# FA_IOTv4_2_1.net
KiCad netlist of a schematic drawn in EAGLE
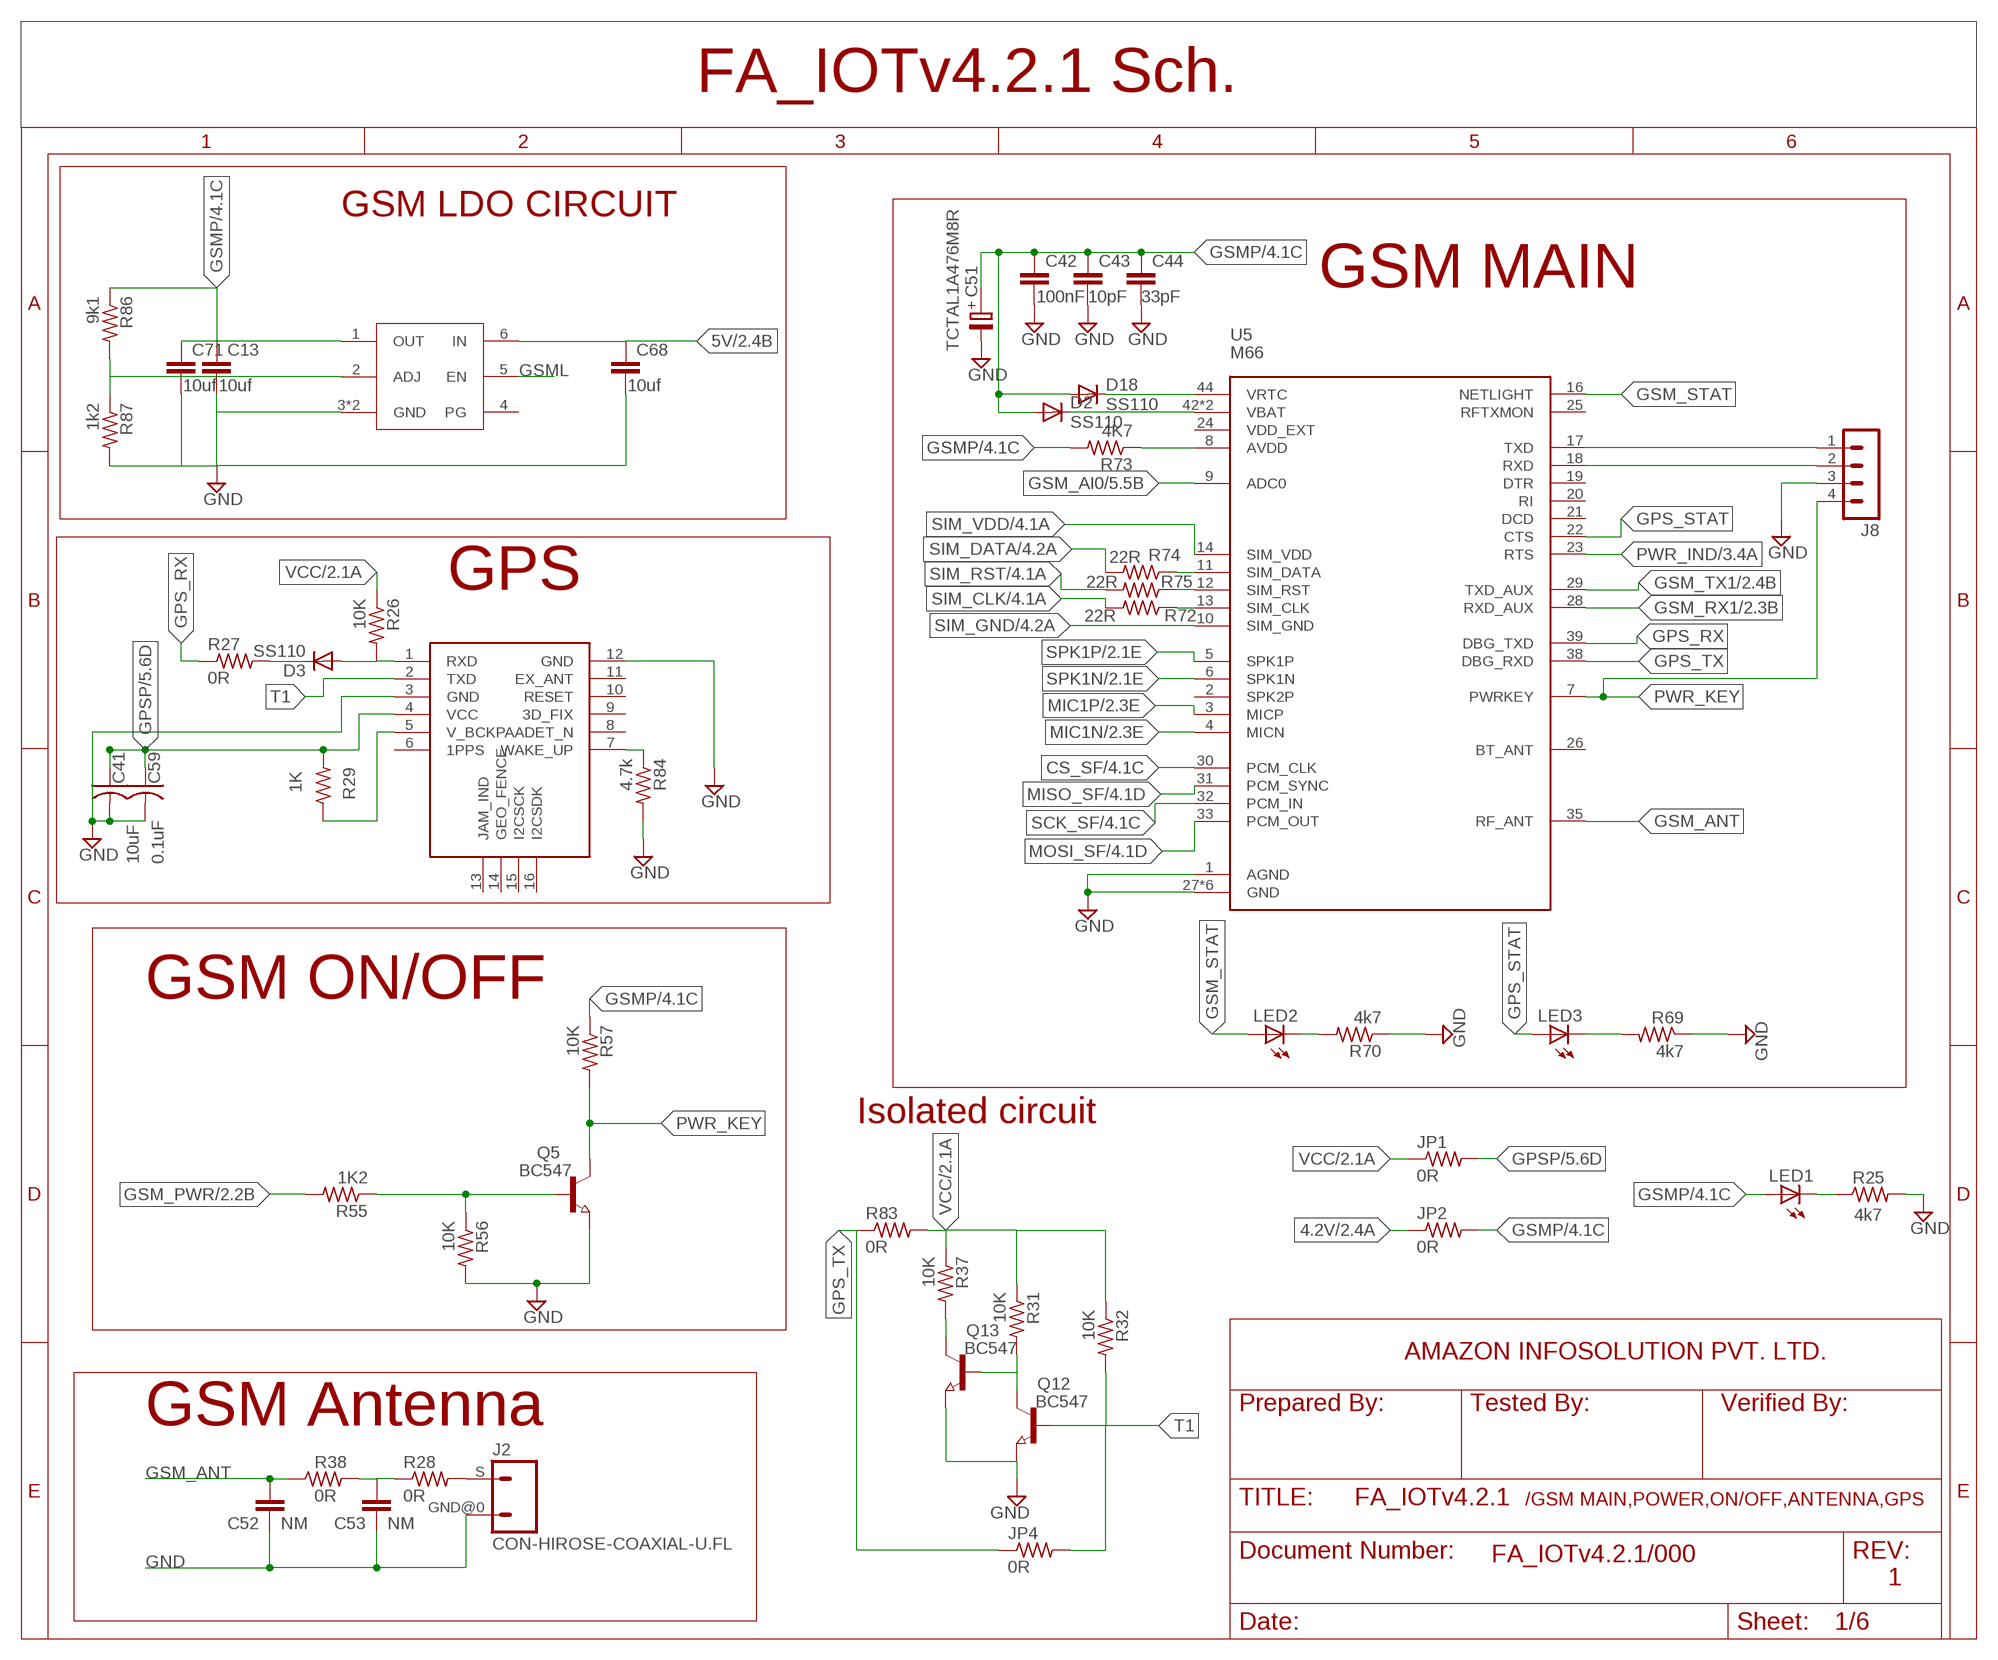
[diagram p0: schematic, sheet 1]
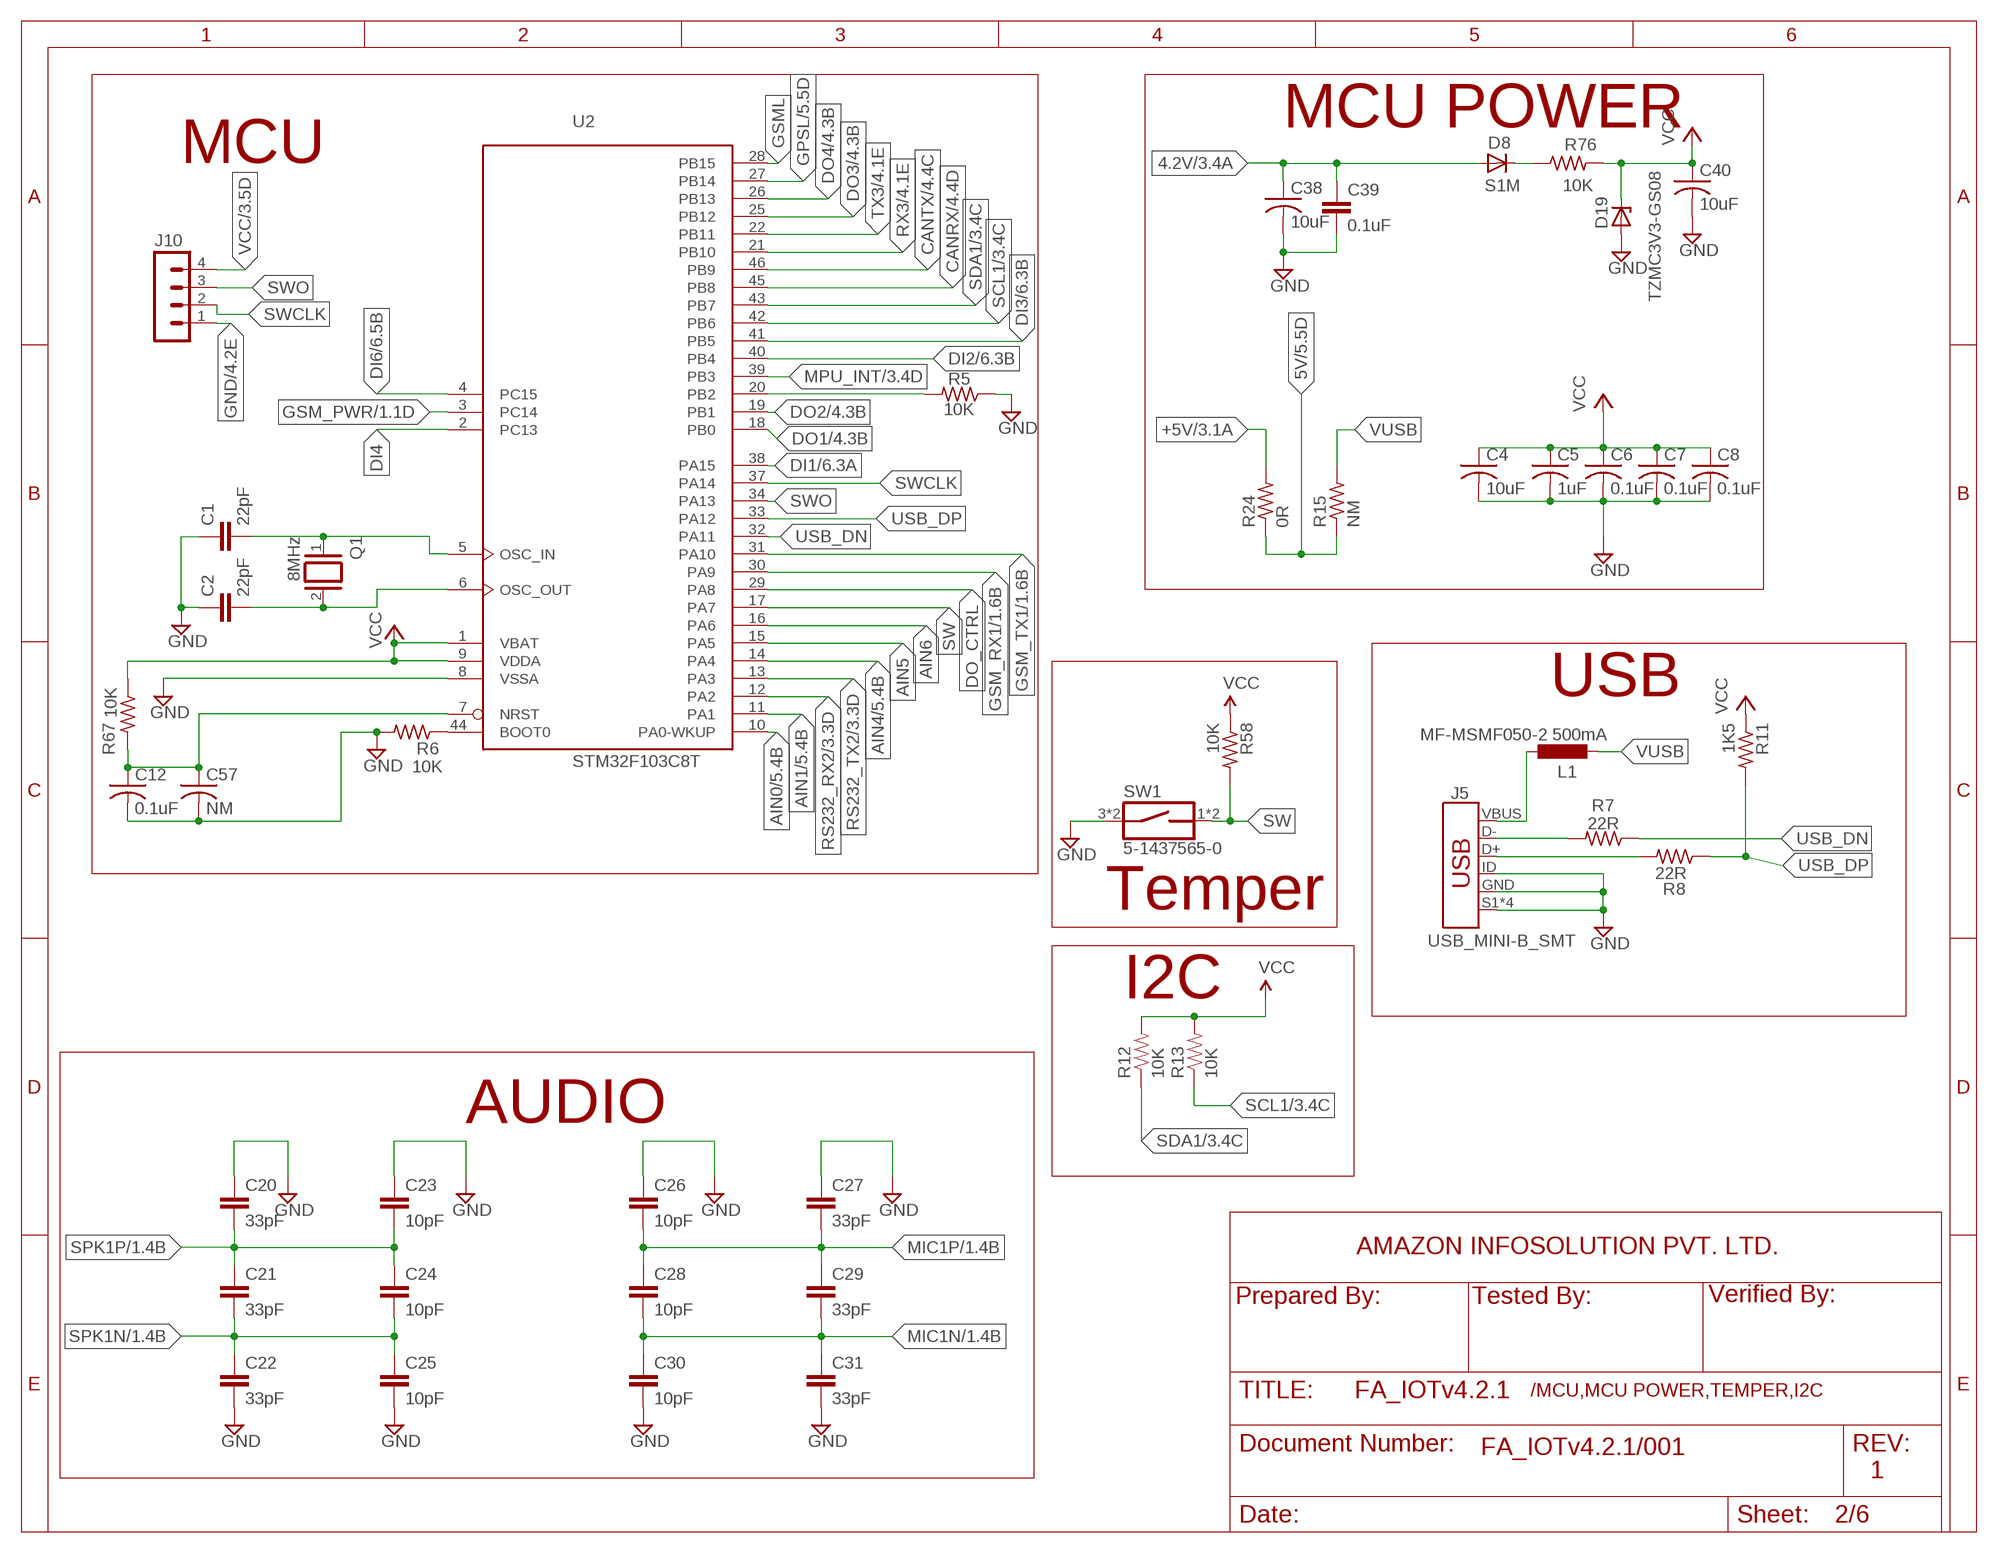
[diagram p1: schematic, sheet 2]
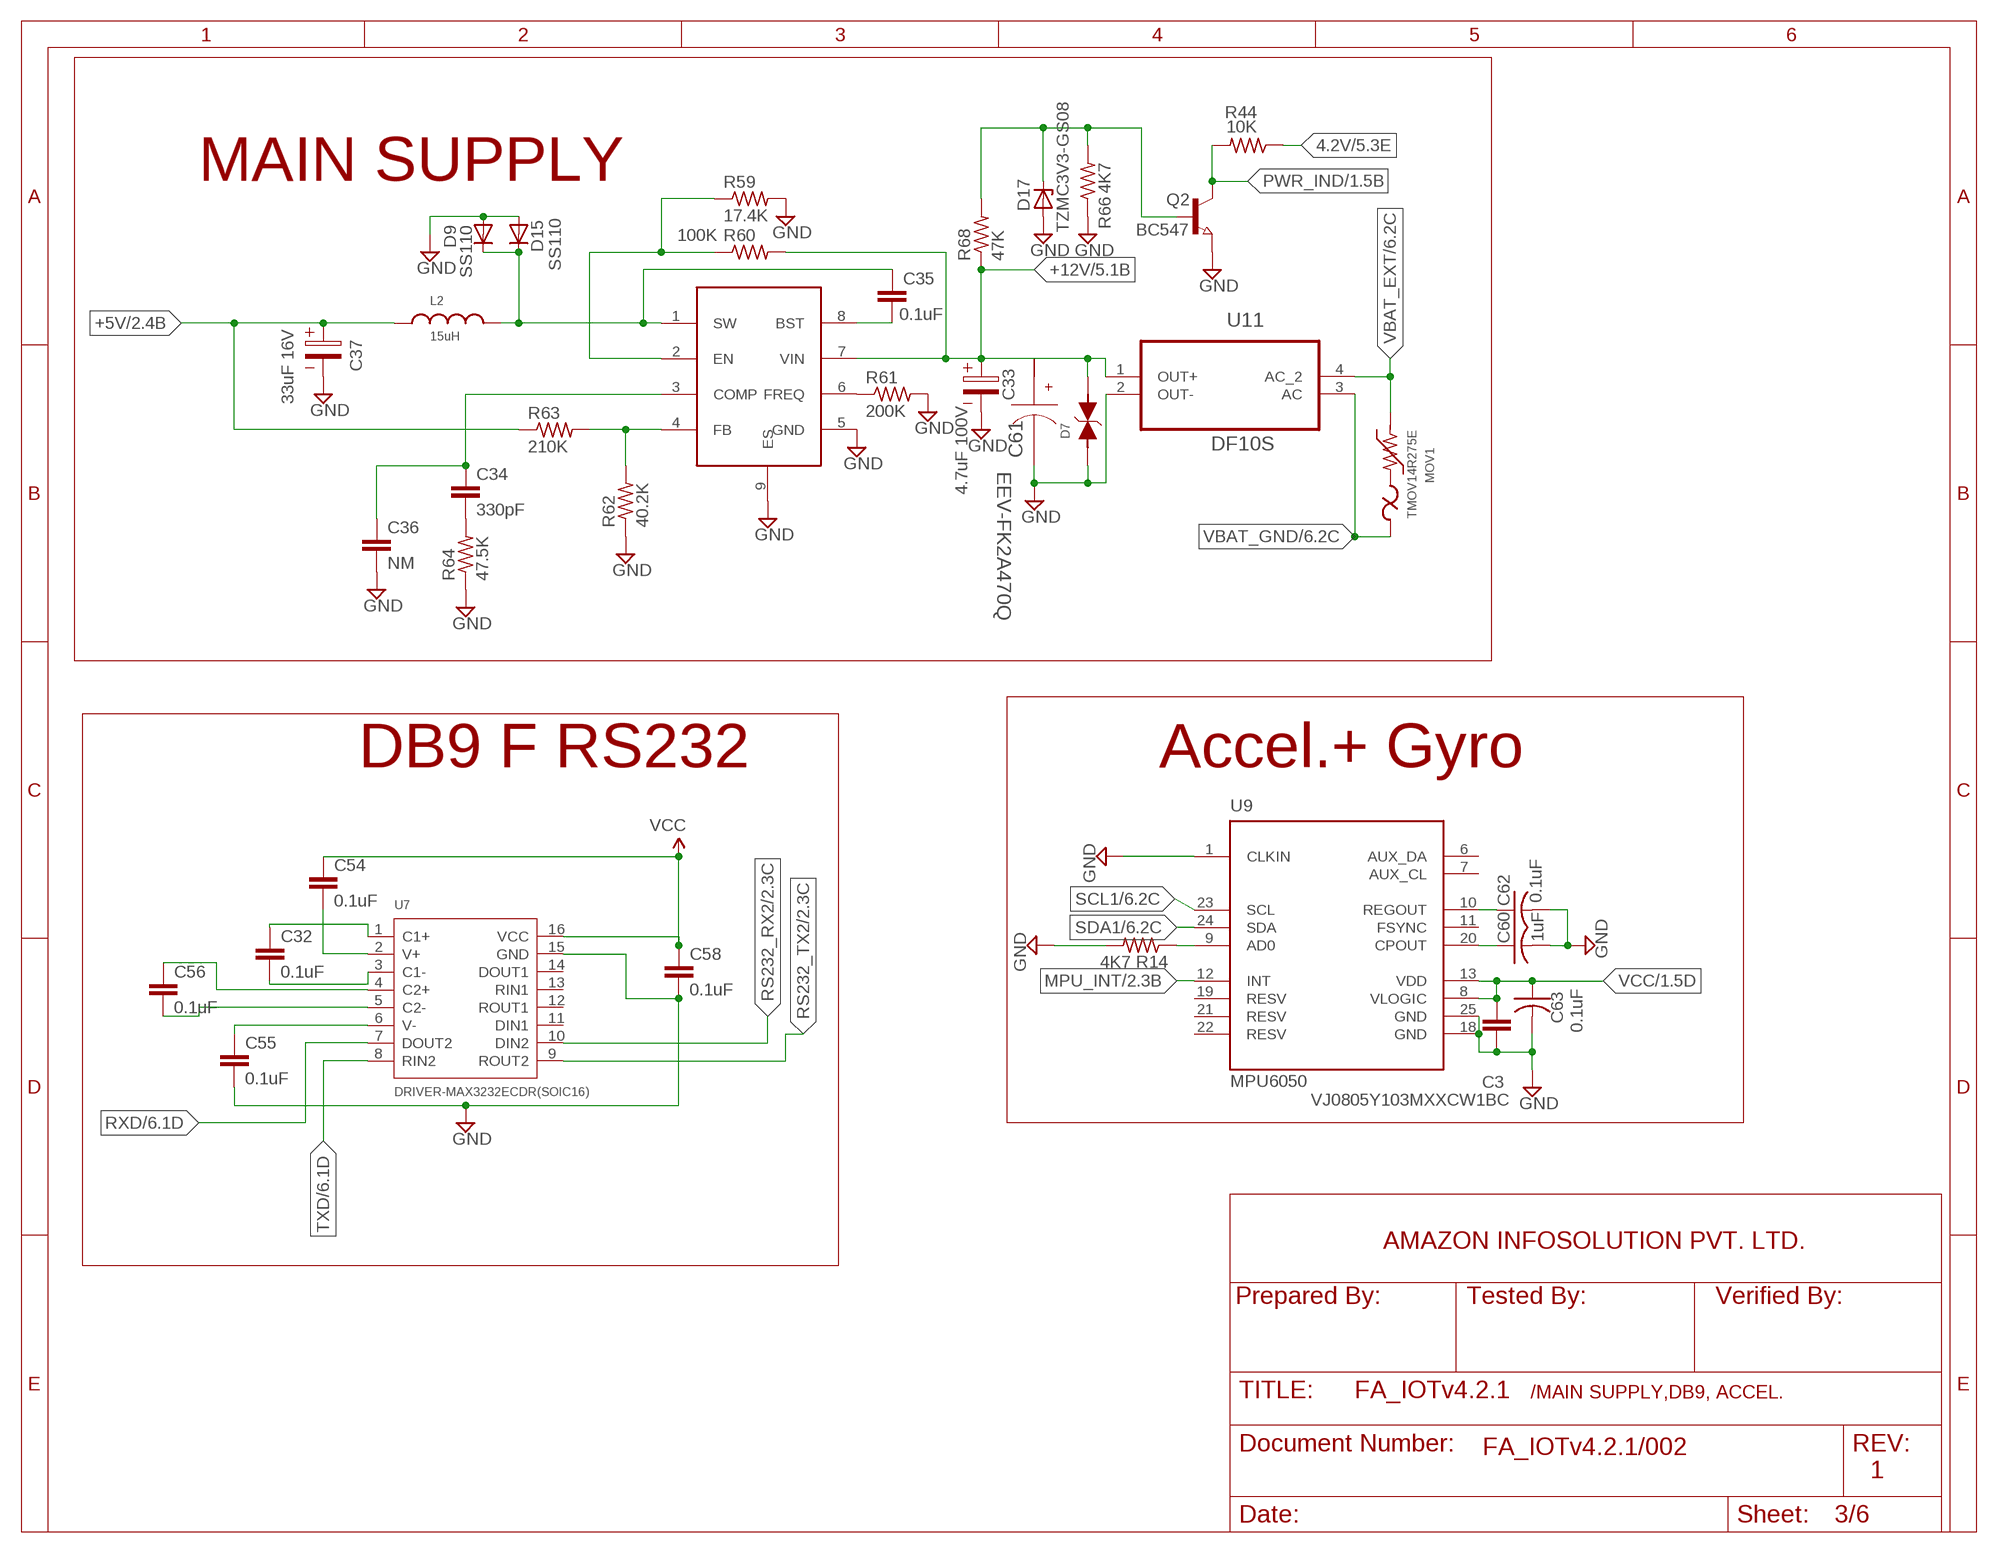
[diagram p2: schematic, sheet 3]
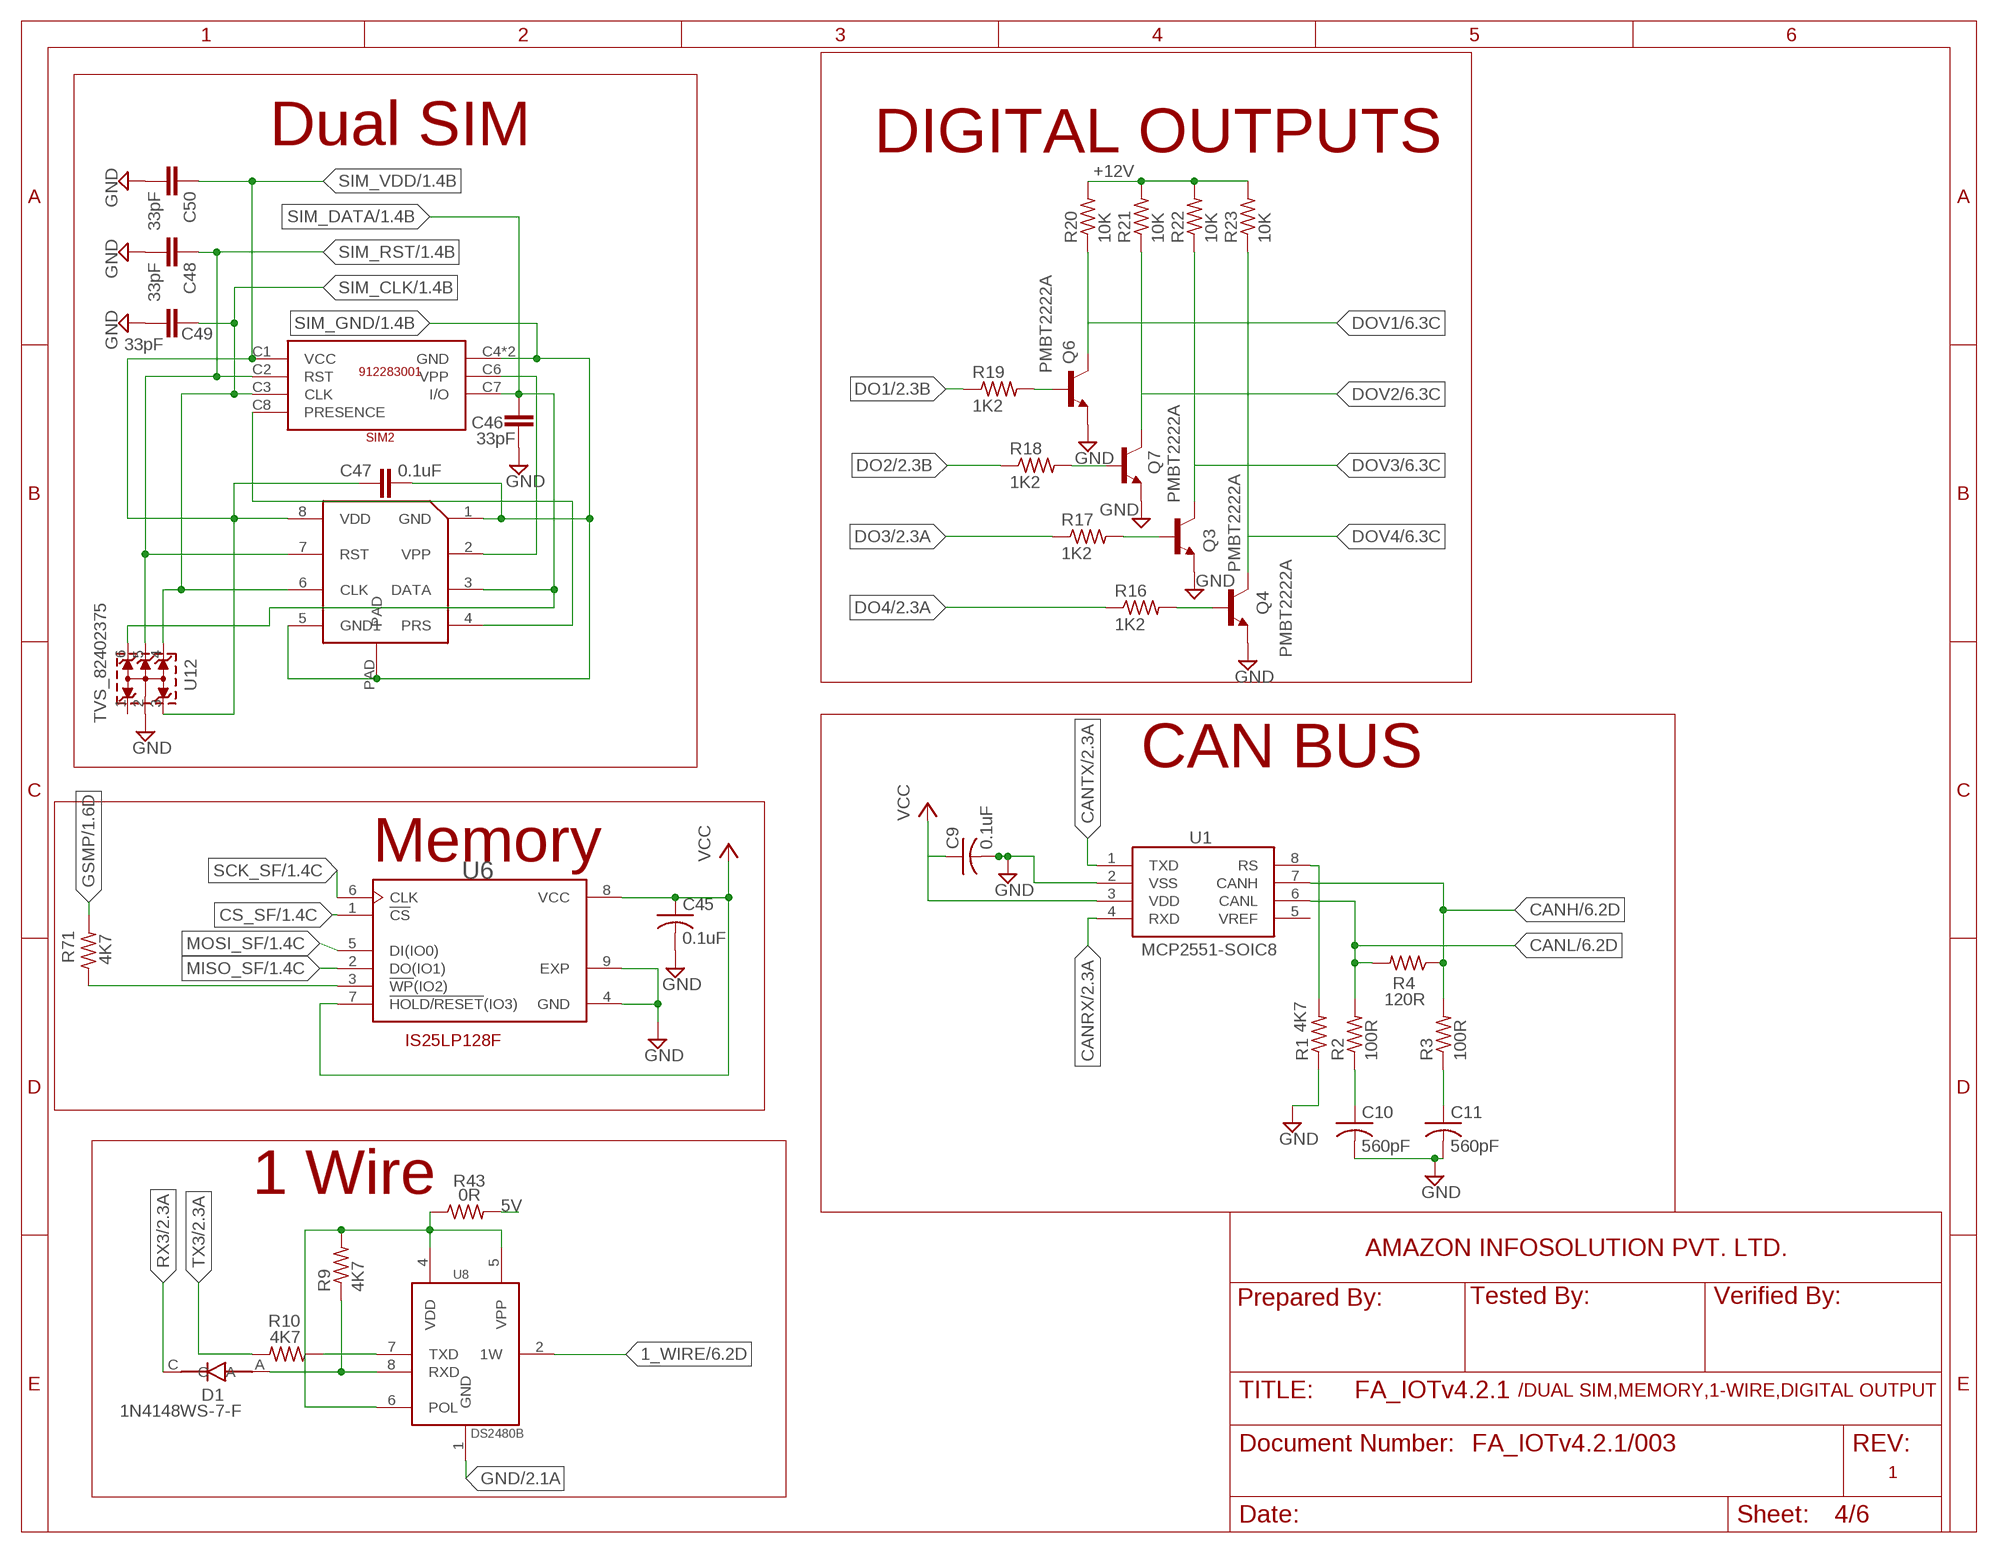
[diagram p3: schematic, sheet 4]
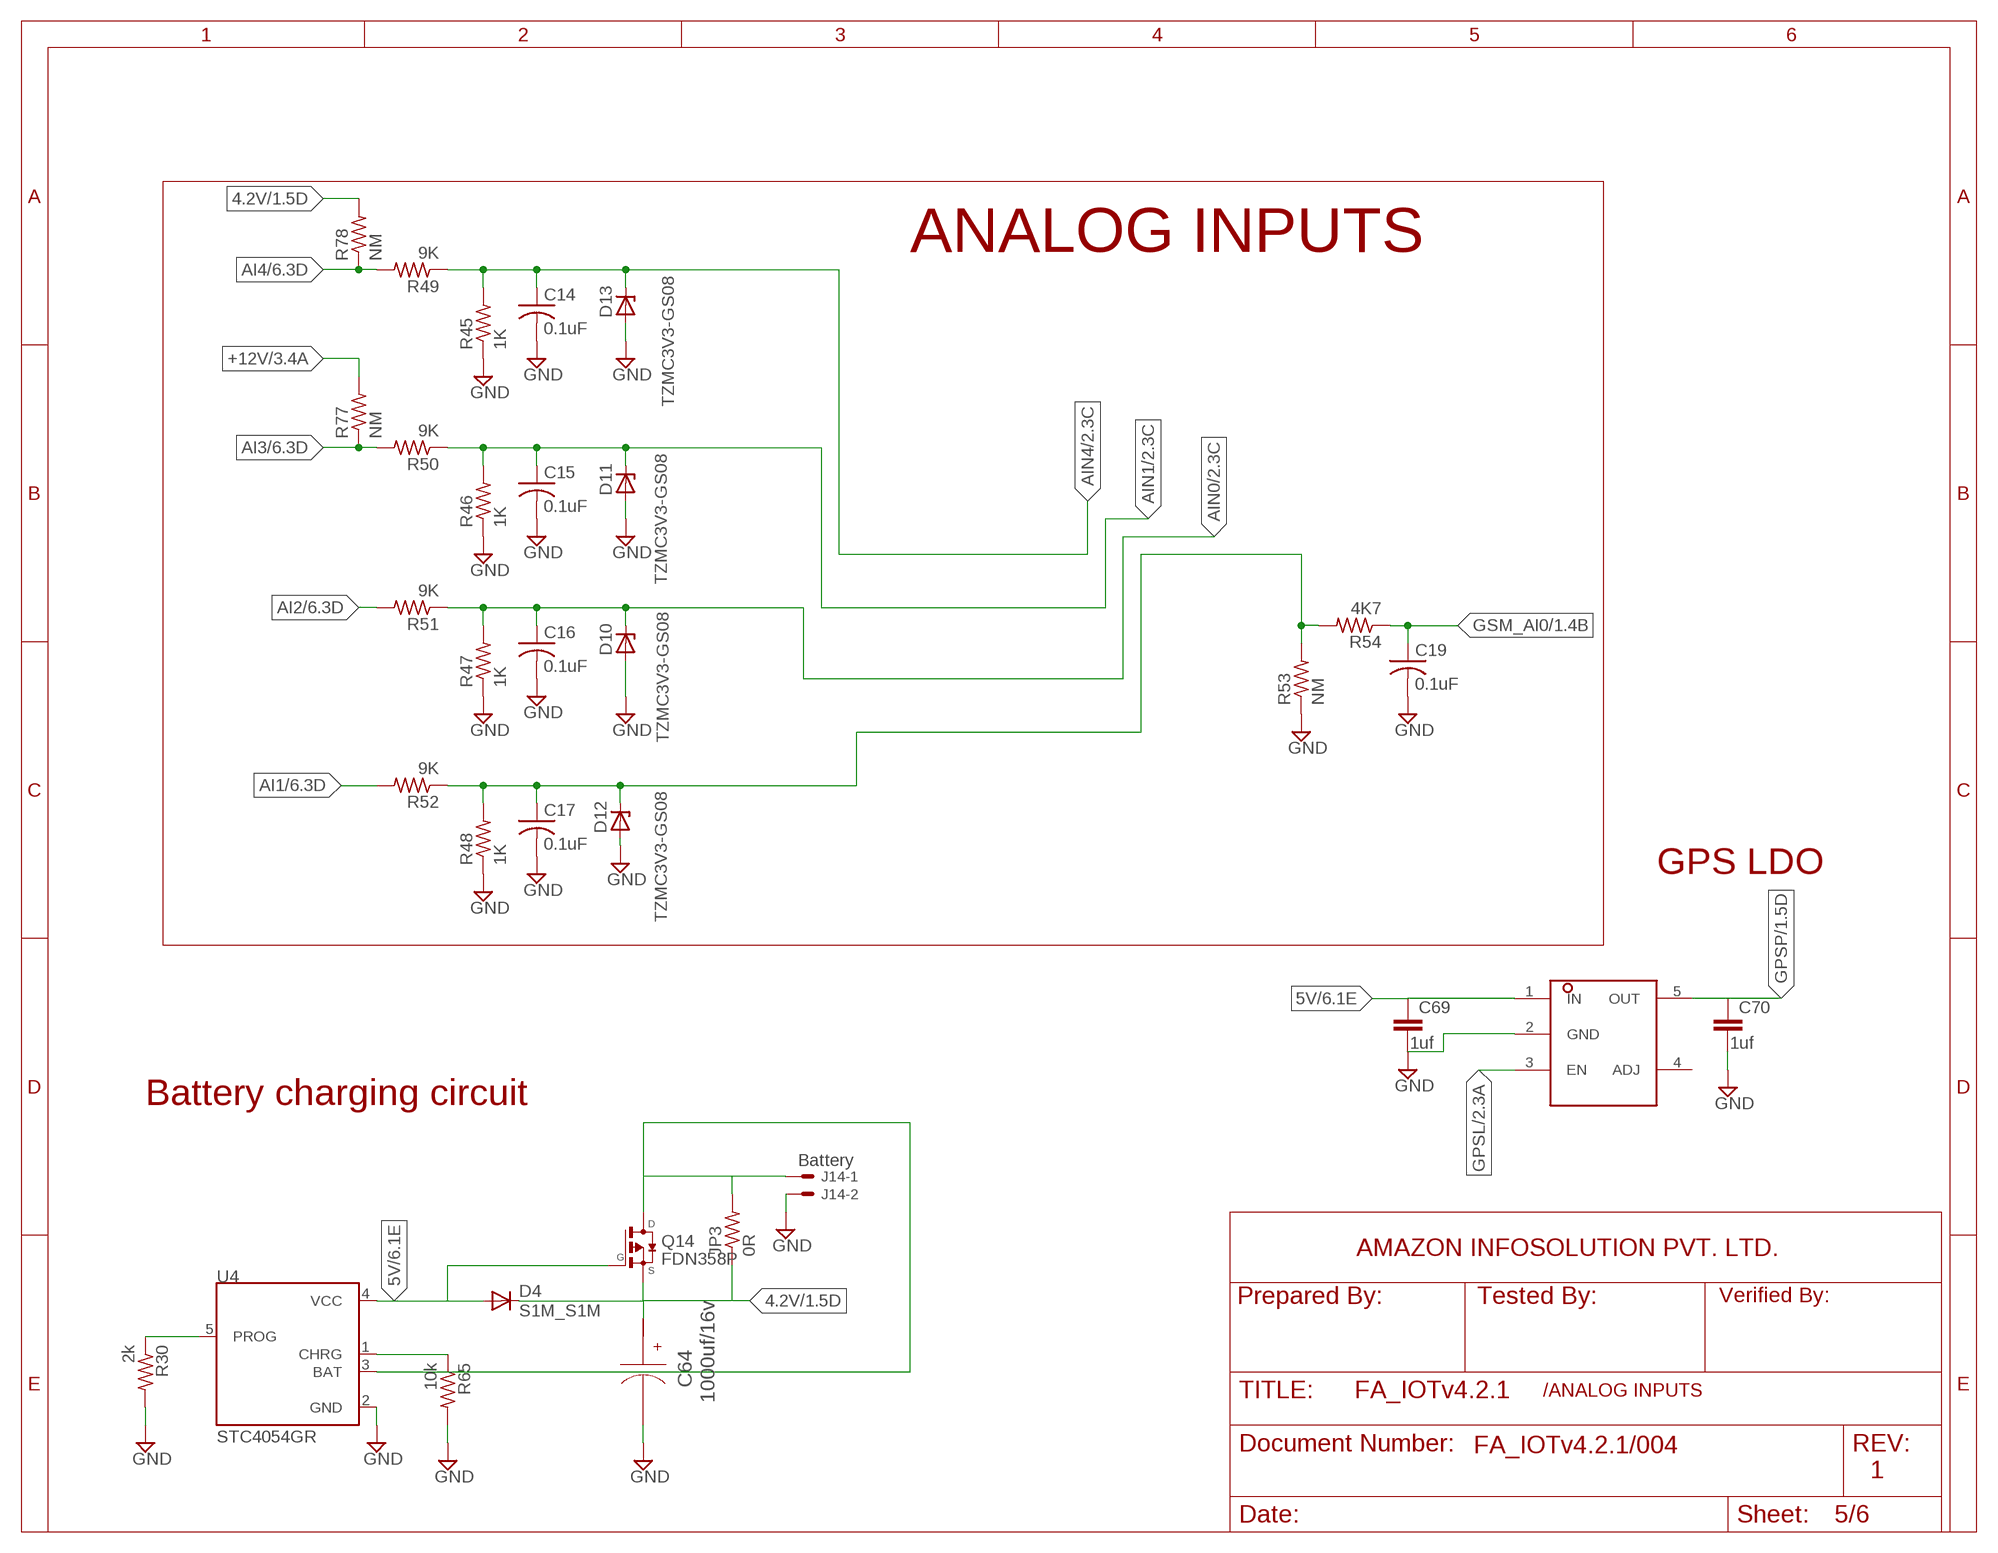
[diagram p4: schematic, sheet 5]
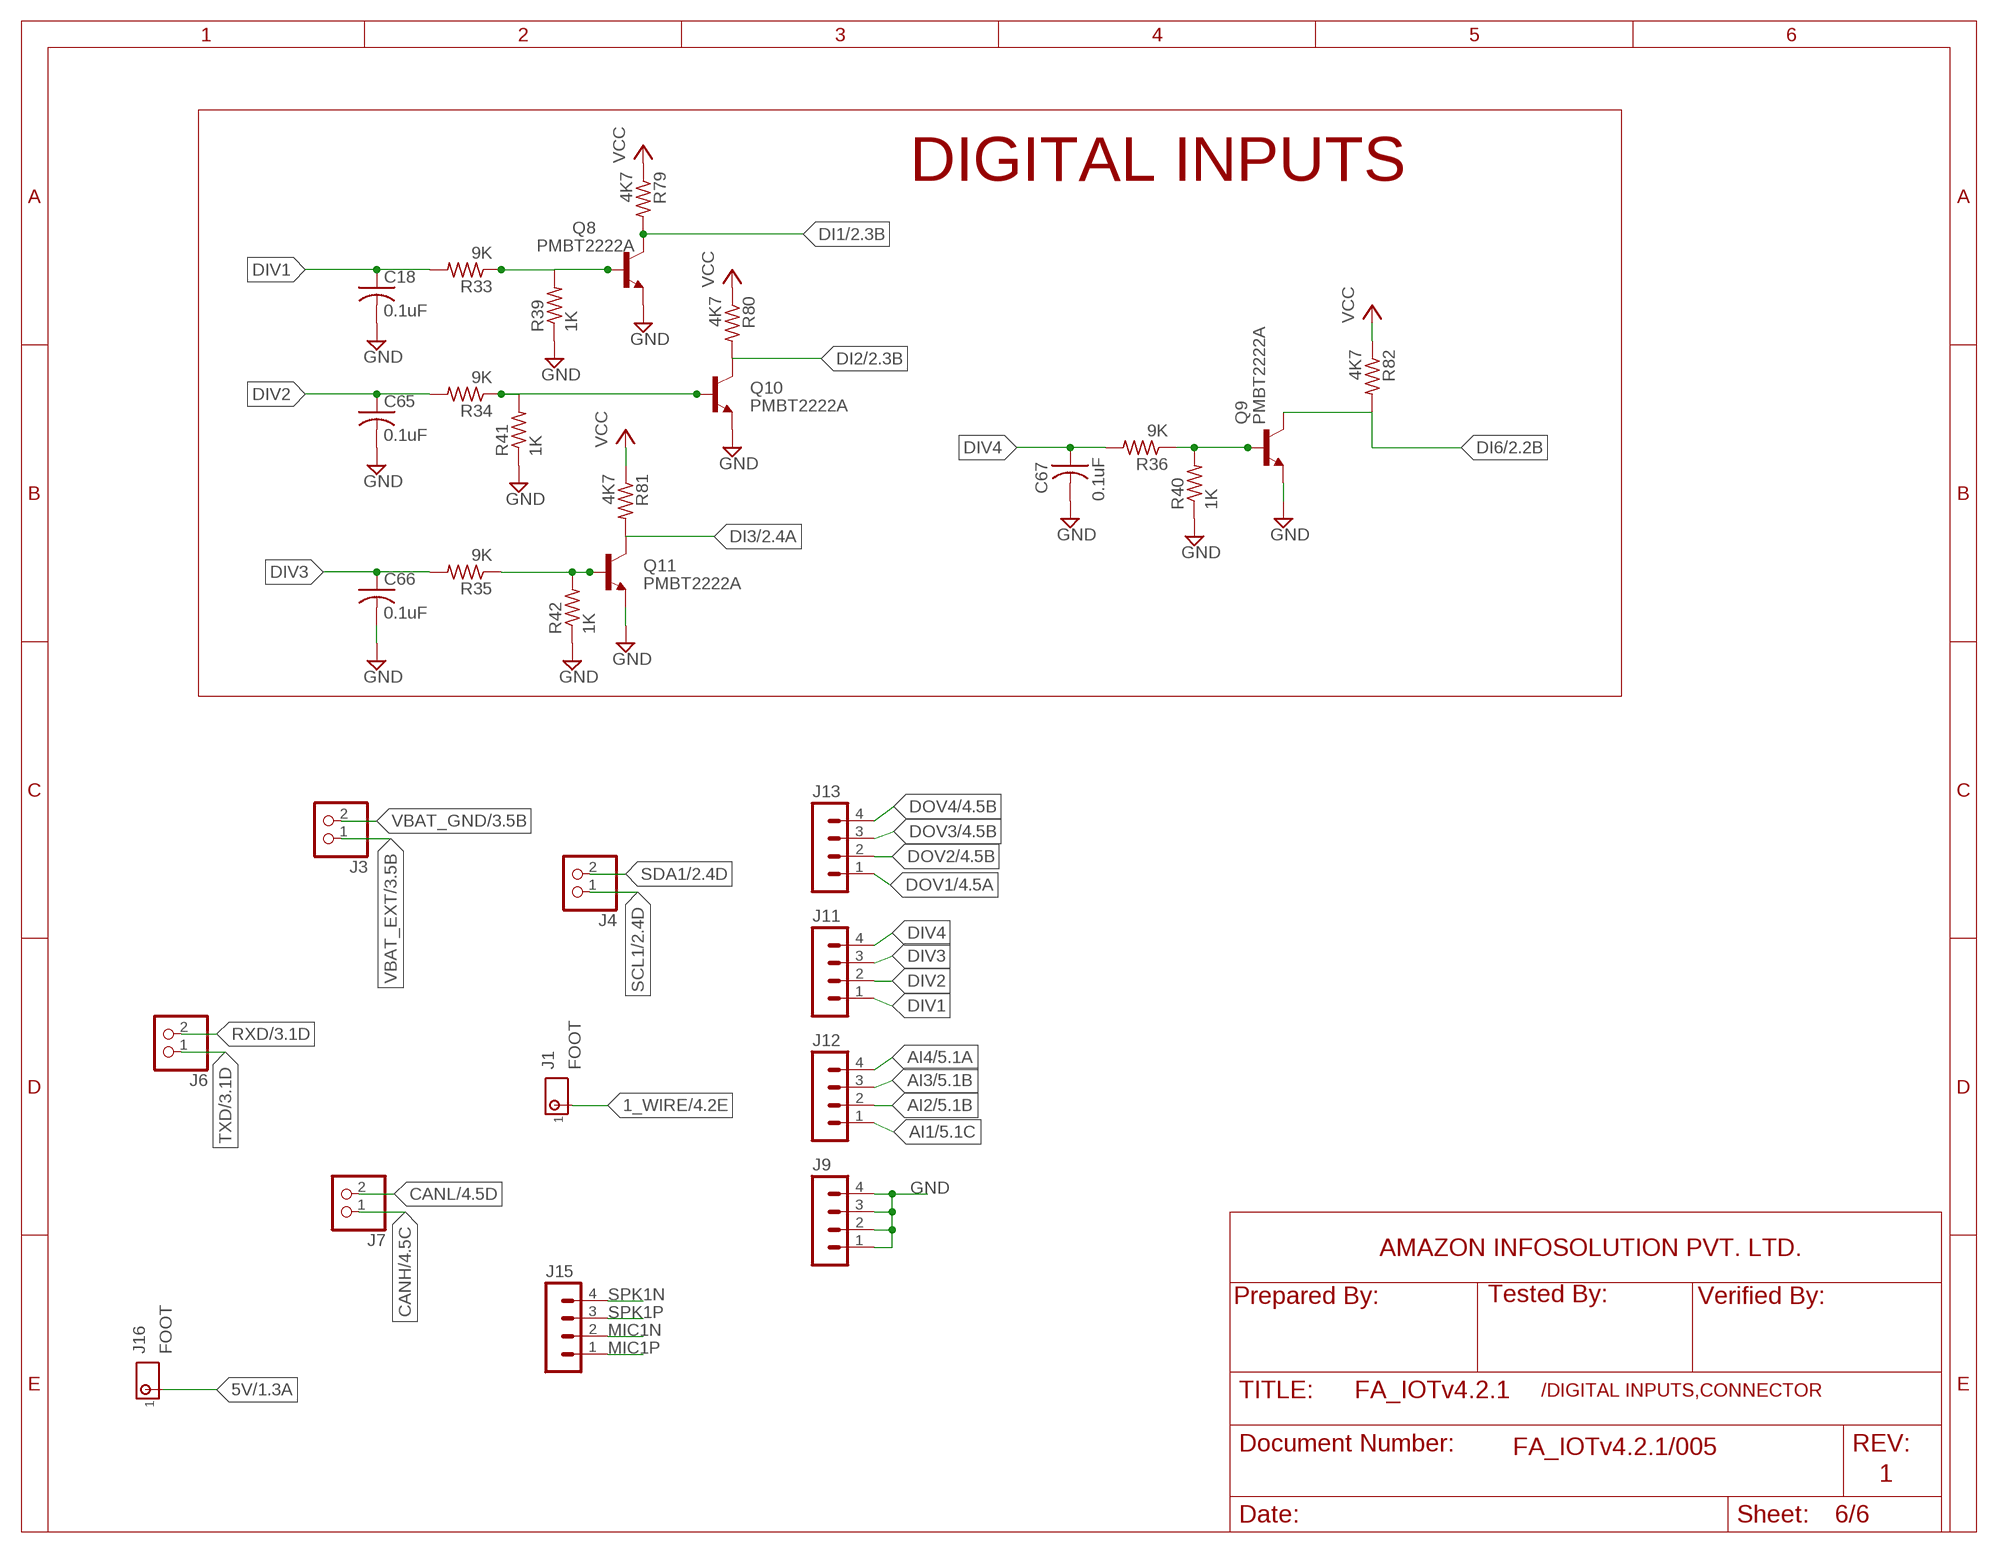
[diagram p5: schematic, sheet 6]

(export (version "E")
  (design (tool "Eeschema 10.0.6"))
  (components
    (comp (ref "C13")
      (value "10uf")
      (footprint "eagle-import:C0805")
      (libsource (lib "eagle-import") (part "resistor_C-EUC0805"))
    )
    (comp (ref "C41")
      (value "10uF")
      (footprint "eagle-import:C0805")
      (libsource (lib "eagle-import") (part "C-USC0805"))
    )
    (comp (ref "C42")
      (value "100nF")
      (footprint "eagle-import:C0805")
      (libsource (lib "eagle-import") (part "resistor_C-EUC0805"))
    )
    (comp (ref "C43")
      (value "10pF")
      (footprint "eagle-import:C0805")
      (libsource (lib "eagle-import") (part "resistor_C-EUC0805"))
    )
    (comp (ref "C44")
      (value "33pF")
      (footprint "eagle-import:C0805")
      (libsource (lib "eagle-import") (part "resistor_C-EUC0805"))
    )
    (comp (ref "C51")
      (value "TCTAL1A476M8R")
      (footprint "eagle-import:TE-A-3216")
      (libsource (lib "eagle-import") (part "C-PR-SMD-TE-A"))
    )
    (comp (ref "C52")
      (value "NM")
      (footprint "eagle-import:C0402")
      (libsource (lib "eagle-import") (part "C-EUC0402"))
    )
    (comp (ref "C53")
      (value "NM")
      (footprint "eagle-import:C0402")
      (libsource (lib "eagle-import") (part "C-EUC0402"))
    )
    (comp (ref "C59")
      (value "0.1uF")
      (footprint "eagle-import:C0402")
      (libsource (lib "eagle-import") (part "C-USC0402"))
    )
    (comp (ref "C68")
      (value "10uf")
      (footprint "eagle-import:C0805")
      (libsource (lib "eagle-import") (part "resistor_C-EUC0805"))
    )
    (comp (ref "C71")
      (value "10uf")
      (footprint "eagle-import:C0805")
      (libsource (lib "eagle-import") (part "resistor_C-EUC0805"))
    )
    (comp (ref "D2")
      (value "SS110")
      (footprint "eagle-import:DO-214AC")
      (fields (field (name "MF") "ON Semiconductor") (field (name "MP") "S1M"))
      (libsource (lib "eagle-import") (part "S1M_S1M"))
    )
    (comp (ref "D3")
      (value "SS110")
      (footprint "eagle-import:DO-214AC")
      (fields (field (name "MF") "ON Semiconductor") (field (name "MP") "S1M"))
      (libsource (lib "eagle-import") (part "S1M_S1M"))
    )
    (comp (ref "D18")
      (value "SS110")
      (footprint "eagle-import:DO-214AC")
      (fields (field (name "MF") "ON Semiconductor") (field (name "MP") "S1M"))
      (libsource (lib "eagle-import") (part "S1M_S1M"))
    )
    (comp (ref "J2")
      (value "CON-HIROSE-COAXIAL-U.FL")
      (footprint "eagle-import:CON-U.FL")
      (libsource (lib "eagle-import") (part "CON-HIROSE-COAXIAL-U.FL"))
    )
    (comp (ref "J8")
      (value "MA04-1")
      (footprint "eagle-import:MA04-1")
      (libsource (lib "eagle-import") (part "MA04-1"))
    )
    (comp (ref "JP1")
      (value "0R")
      (footprint "eagle-import:R0805")
      (libsource (lib "eagle-import") (part "resistor_R-US_R0805"))
    )
    (comp (ref "JP2")
      (value "0R")
      (footprint "eagle-import:R0805")
      (libsource (lib "eagle-import") (part "resistor_R-US_R0805"))
    )
    (comp (ref "JP4")
      (value "0R")
      (footprint "eagle-import:R0805")
      (libsource (lib "eagle-import") (part "resistor_R-US_R0805"))
    )
    (comp (ref "LED1")
      (value "LEDCHIP-LED0805")
      (footprint "eagle-import:CHIP-LED0805")
      (libsource (lib "eagle-import") (part "LEDCHIP-LED0805"))
    )
    (comp (ref "LED2")
      (value "LEDCHIP-LED0805")
      (footprint "eagle-import:CHIP-LED0805")
      (libsource (lib "eagle-import") (part "LEDCHIP-LED0805"))
    )
    (comp (ref "LED3")
      (value "LEDCHIP-LED0805")
      (footprint "eagle-import:CHIP-LED0805")
      (libsource (lib "eagle-import") (part "LEDCHIP-LED0805"))
    )
    (comp (ref "Q5")
      (value "BC547")
      (footprint "eagle-import:SOT23")
      (libsource (lib "eagle-import") (part "NPN-TRANSISTOR_SOT23"))
    )
    (comp (ref "Q12")
      (value "BC547")
      (footprint "eagle-import:SOT23")
      (libsource (lib "eagle-import") (part "NPN-TRANSISTOR_SOT23"))
    )
    (comp (ref "Q13")
      (value "BC547")
      (footprint "eagle-import:SOT23")
      (libsource (lib "eagle-import") (part "NPN-TRANSISTOR_SOT23"))
    )
    (comp (ref "R25")
      (value "4k7")
      (footprint "eagle-import:R0402")
      (libsource (lib "eagle-import") (part "R-US_R0402"))
    )
    (comp (ref "R26")
      (value "10K")
      (footprint "eagle-import:R0402")
      (libsource (lib "eagle-import") (part "resistor_R-US_R0402"))
    )
    (comp (ref "R27")
      (value "0R")
      (footprint "eagle-import:R0805")
      (libsource (lib "eagle-import") (part "resistor_R-US_R0805"))
    )
    (comp (ref "R28")
      (value "0R")
      (footprint "eagle-import:R0402")
      (libsource (lib "eagle-import") (part "resistor_R-US_R0402"))
    )
    (comp (ref "R29")
      (value "1K")
      (footprint "eagle-import:R0402")
      (libsource (lib "eagle-import") (part "resistor_R-US_R0402"))
    )
    (comp (ref "R31")
      (value "10K")
      (footprint "eagle-import:R0402")
      (libsource (lib "eagle-import") (part "resistor_R-US_R0402"))
    )
    (comp (ref "R32")
      (value "10K")
      (footprint "eagle-import:R0402")
      (libsource (lib "eagle-import") (part "resistor_R-US_R0402"))
    )
    (comp (ref "R37")
      (value "10K")
      (footprint "eagle-import:R0402")
      (libsource (lib "eagle-import") (part "resistor_R-US_R0402"))
    )
    (comp (ref "R38")
      (value "0R")
      (footprint "eagle-import:R0402")
      (libsource (lib "eagle-import") (part "resistor_R-US_R0402"))
    )
    (comp (ref "R55")
      (value "1K2")
      (footprint "eagle-import:R0402")
      (libsource (lib "eagle-import") (part "resistor_R-US_R0402"))
    )
    (comp (ref "R56")
      (value "10K")
      (footprint "eagle-import:R0402")
      (libsource (lib "eagle-import") (part "resistor_R-US_R0402"))
    )
    (comp (ref "R57")
      (value "10K")
      (footprint "eagle-import:R0402")
      (libsource (lib "eagle-import") (part "resistor_R-US_R0402"))
    )
    (comp (ref "R69")
      (value "4k7")
      (footprint "eagle-import:R0402")
      (libsource (lib "eagle-import") (part "R-US_R0402"))
    )
    (comp (ref "R70")
      (value "4k7")
      (footprint "eagle-import:R0402")
      (libsource (lib "eagle-import") (part "R-US_R0402"))
    )
    (comp (ref "R72")
      (value "22R")
      (footprint "eagle-import:R0402")
      (libsource (lib "eagle-import") (part "resistor_R-US_R0402"))
    )
    (comp (ref "R73")
      (value "4K7")
      (footprint "eagle-import:R0402")
      (libsource (lib "eagle-import") (part "resistor_R-US_R0402"))
    )
    (comp (ref "R74")
      (value "22R")
      (footprint "eagle-import:R0402")
      (libsource (lib "eagle-import") (part "resistor_R-US_R0402"))
    )
    (comp (ref "R75")
      (value "22R")
      (footprint "eagle-import:R0402")
      (libsource (lib "eagle-import") (part "resistor_R-US_R0402"))
    )
    (comp (ref "R83")
      (value "0R")
      (footprint "eagle-import:R0805")
      (libsource (lib "eagle-import") (part "resistor_R-US_R0805"))
    )
    (comp (ref "R84")
      (value "4.7k")
      (footprint "eagle-import:R0402")
      (libsource (lib "eagle-import") (part "resistor_R-US_R0402"))
    )
    (comp (ref "R86")
      (value "9k1")
      (footprint "eagle-import:R0402")
      (libsource (lib "eagle-import") (part "resistor_R-US_R0402"))
    )
    (comp (ref "R87")
      (value "1k2")
      (footprint "eagle-import:R0402")
      (libsource (lib "eagle-import") (part "resistor_R-US_R0402"))
    )
    (comp (ref "U$1")
      (value "L89")
      (footprint "eagle-import:L89")
      (libsource (lib "eagle-import") (part "L89"))
    )
    (comp (ref "U$3")
      (value "LD39200PU33R")
      (footprint "eagle-import:SON95P300X300X100-7N")
      (fields (field (name "MF") "STMicroelectronics"))
      (libsource (lib "eagle-import") (part "LD39200PU33R"))
    )
    (comp (ref "U5")
      (value "M66")
      (footprint "eagle-import:M66")
      (libsource (lib "eagle-import") (part "M66"))
    )
    (comp (ref "C9")
      (value "0.1uF")
      (footprint "eagle-import:C0805")
      (libsource (lib "eagle-import") (part "C-USC0805"))
    )
    (comp (ref "C10")
      (value "560pF")
      (footprint "eagle-import:C0402")
      (libsource (lib "eagle-import") (part "C-USC0402"))
    )
    (comp (ref "C11")
      (value "560pF")
      (footprint "eagle-import:C0402")
      (libsource (lib "eagle-import") (part "C-USC0402"))
    )
    (comp (ref "C45")
      (value "0.1uF")
      (footprint "eagle-import:C0402")
      (libsource (lib "eagle-import") (part "C-USC0402"))
    )
    (comp (ref "C46")
      (value "33pF")
      (footprint "eagle-import:C0805")
      (libsource (lib "eagle-import") (part "resistor_C-EUC0805"))
    )
    (comp (ref "C47")
      (value "0.1uF")
      (footprint "eagle-import:C0805")
      (libsource (lib "eagle-import") (part "resistor_C-EUC0805"))
    )
    (comp (ref "C48")
      (value "33pF")
      (footprint "eagle-import:C0805")
      (libsource (lib "eagle-import") (part "resistor_C-EUC0805"))
    )
    (comp (ref "C49")
      (value "33pF")
      (footprint "eagle-import:C0805")
      (libsource (lib "eagle-import") (part "resistor_C-EUC0805"))
    )
    (comp (ref "C50")
      (value "33pF")
      (footprint "eagle-import:C0805")
      (libsource (lib "eagle-import") (part "resistor_C-EUC0805"))
    )
    (comp (ref "D1")
      (value "1N4148WS-7-F")
      (footprint "eagle-import:SOD2513X120N")
      (fields (field (name "MF") "Diodes Inc."))
      (libsource (lib "eagle-import") (part "1N4148WS-7-F"))
    )
    (comp (ref "Q3")
      (value "PMBT2222A")
      (footprint "eagle-import:SOT23-BEC")
      (fields (field (name "MF") "NXP Semiconductors"))
      (libsource (lib "eagle-import") (part "PMBT2222A"))
    )
    (comp (ref "Q4")
      (value "PMBT2222A")
      (footprint "eagle-import:SOT23-BEC")
      (fields (field (name "MF") "NXP Semiconductors"))
      (libsource (lib "eagle-import") (part "PMBT2222A"))
    )
    (comp (ref "Q6")
      (value "PMBT2222A")
      (footprint "eagle-import:SOT23-BEC")
      (fields (field (name "MF") "NXP Semiconductors"))
      (libsource (lib "eagle-import") (part "PMBT2222A"))
    )
    (comp (ref "Q7")
      (value "PMBT2222A")
      (footprint "eagle-import:SOT23-BEC")
      (fields (field (name "MF") "NXP Semiconductors"))
      (libsource (lib "eagle-import") (part "PMBT2222A"))
    )
    (comp (ref "R1")
      (value "4K7")
      (footprint "eagle-import:R0402")
      (libsource (lib "eagle-import") (part "resistor_R-US_R0402"))
    )
    (comp (ref "R2")
      (value "100R")
      (footprint "eagle-import:R0402")
      (libsource (lib "eagle-import") (part "resistor_R-US_R0402"))
    )
    (comp (ref "R3")
      (value "100R")
      (footprint "eagle-import:R0402")
      (libsource (lib "eagle-import") (part "resistor_R-US_R0402"))
    )
    (comp (ref "R4")
      (value "120R")
      (footprint "eagle-import:R0402")
      (libsource (lib "eagle-import") (part "resistor_R-US_R0402"))
    )
    (comp (ref "R9")
      (value "4K7")
      (footprint "eagle-import:R0402")
      (libsource (lib "eagle-import") (part "resistor_R-US_R0402"))
    )
    (comp (ref "R10")
      (value "4K7")
      (footprint "eagle-import:R0402")
      (libsource (lib "eagle-import") (part "resistor_R-US_R0402"))
    )
    (comp (ref "R16")
      (value "1K2")
      (footprint "eagle-import:R0402")
      (libsource (lib "eagle-import") (part "resistor_R-US_R0402"))
    )
    (comp (ref "R17")
      (value "1K2")
      (footprint "eagle-import:R0402")
      (libsource (lib "eagle-import") (part "resistor_R-US_R0402"))
    )
    (comp (ref "R18")
      (value "1K2")
      (footprint "eagle-import:R0402")
      (libsource (lib "eagle-import") (part "resistor_R-US_R0402"))
    )
    (comp (ref "R19")
      (value "1K2")
      (footprint "eagle-import:R0402")
      (libsource (lib "eagle-import") (part "resistor_R-US_R0402"))
    )
    (comp (ref "R20")
      (value "10K")
      (footprint "eagle-import:R0805")
      (libsource (lib "eagle-import") (part "resistor_R-US_R0805"))
    )
    (comp (ref "R21")
      (value "10K")
      (footprint "eagle-import:R0805")
      (libsource (lib "eagle-import") (part "resistor_R-US_R0805"))
    )
    (comp (ref "R22")
      (value "10K")
      (footprint "eagle-import:R0805")
      (libsource (lib "eagle-import") (part "resistor_R-US_R0805"))
    )
    (comp (ref "R23")
      (value "10K")
      (footprint "eagle-import:R0805")
      (libsource (lib "eagle-import") (part "resistor_R-US_R0805"))
    )
    (comp (ref "R43")
      (value "0R")
      (footprint "eagle-import:R0805")
      (libsource (lib "eagle-import") (part "resistor_R-US_R0805"))
    )
    (comp (ref "R71")
      (value "4K7")
      (footprint "eagle-import:R0402")
      (libsource (lib "eagle-import") (part "R-US_R0402"))
    )
    (comp (ref "SIM1")
      (value "MFF2_SIM")
      (footprint "eagle-import:MFF2DFN8")
      (libsource (lib "eagle-import") (part "MFF2_SIM"))
    )
    (comp (ref "SIM2")
      (value "912283001")
      (footprint "eagle-import:91228-3001")
      (fields (field (name "MF") "Molex") (field (name "MP") "91228-3001"))
      (libsource (lib "eagle-import") (part "912283001"))
    )
    (comp (ref "U1")
      (value "MCP2551-SOIC8")
      (footprint "eagle-import:SOIC8-6.0")
      (libsource (lib "eagle-import") (part "MCP2551-SOIC8"))
    )
    (comp (ref "U6")
      (value "W25Q32FVZPIG_TR")
      (footprint "eagle-import:SON127P600X500X80-9N")
      (fields (field (name "MF") "Winbond") (field (name "MP") "W25Q32FVZPIG TR"))
      (libsource (lib "eagle-import") (part "W25Q32FVZPIG_TR"))
    )
    (comp (ref "U8")
      (value "DS2480B")
      (footprint "eagle-import:SO08")
      (fields (field (name "MF") "Maxim Integrated"))
      (libsource (lib "eagle-import") (part "DS2480B"))
    )
    (comp (ref "U12")
      (value "TVS_82402375")
      (footprint "eagle-import:WE-TVS_SC70-6L")
      (fields (field (name "MF") "Wurth Electronics") (field (name "MP") "82402375"))
      (libsource (lib "eagle-import") (part "WE-TVS_82402375"))
    )
    (comp (ref "C14")
      (value "0.1uF")
      (footprint "eagle-import:C0402")
      (libsource (lib "eagle-import") (part "C-USC0402"))
    )
    (comp (ref "C15")
      (value "0.1uF")
      (footprint "eagle-import:C0402")
      (libsource (lib "eagle-import") (part "C-USC0402"))
    )
    (comp (ref "C16")
      (value "0.1uF")
      (footprint "eagle-import:C0402")
      (libsource (lib "eagle-import") (part "C-USC0402"))
    )
    (comp (ref "C17")
      (value "0.1uF")
      (footprint "eagle-import:C0402")
      (libsource (lib "eagle-import") (part "C-USC0402"))
    )
    (comp (ref "C19")
      (value "0.1uF")
      (footprint "eagle-import:C0402")
      (libsource (lib "eagle-import") (part "C-USC0402"))
    )
    (comp (ref "C64")
      (value "1000uf/16v")
      (footprint "eagle-import:SM_RADIAL_H13")
      (fields (field (name "MF") "Panasonic") (field (name "MP") "EEV-FK2A470Q"))
      (libsource (lib "eagle-import") (part "EEV-FK2A470Q"))
    )
    (comp (ref "C69")
      (value "1uf")
      (footprint "eagle-import:C0603")
      (libsource (lib "eagle-import") (part "resistor_C-EUC0603"))
    )
    (comp (ref "C70")
      (value "1uf")
      (footprint "eagle-import:C0603")
      (libsource (lib "eagle-import") (part "resistor_C-EUC0603"))
    )
    (comp (ref "D4")
      (value "S1M_S1M")
      (footprint "eagle-import:S1M_DO-214AC")
      (fields (field (name "MF") "ON Semiconductor") (field (name "MP") "S1M"))
      (libsource (lib "eagle-import") (part "S1M_S1M"))
    )
    (comp (ref "D10")
      (value "TZMC3V3-GS08")
      (footprint "eagle-import:SOD80C")
      (libsource (lib "eagle-import") (part "ZENER-DIODESOD80C"))
    )
    (comp (ref "D11")
      (value "TZMC3V3-GS08")
      (footprint "eagle-import:SOD80C")
      (libsource (lib "eagle-import") (part "ZENER-DIODESOD80C"))
    )
    (comp (ref "D12")
      (value "TZMC3V3-GS08")
      (footprint "eagle-import:SOD80C")
      (libsource (lib "eagle-import") (part "ZENER-DIODESOD80C"))
    )
    (comp (ref "D13")
      (value "TZMC3V3-GS08")
      (footprint "eagle-import:SOD80C")
      (libsource (lib "eagle-import") (part "ZENER-DIODESOD80C"))
    )
    (comp (ref "J14")
      (value "Battery")
      (footprint "eagle-import:6410-02")
      (libsource (lib "eagle-import") (part "22-?-0227-2021"))
    )
    (comp (ref "JP3")
      (value "0R")
      (footprint "eagle-import:R0805")
      (libsource (lib "eagle-import") (part "resistor_R-US_R0805"))
    )
    (comp (ref "Q14")
      (value "FDN358P")
      (footprint "eagle-import:SSOT-3")
      (fields (field (name "MF") "ON Semiconductor"))
      (libsource (lib "eagle-import") (part "FDN358P"))
    )
    (comp (ref "R30")
      (value "2k")
      (footprint "eagle-import:R0402")
      (libsource (lib "eagle-import") (part "resistor_R-US_R0402"))
    )
    (comp (ref "R45")
      (value "1K")
      (footprint "eagle-import:R0402")
      (libsource (lib "eagle-import") (part "resistor_R-US_R0402"))
    )
    (comp (ref "R46")
      (value "1K")
      (footprint "eagle-import:R0402")
      (libsource (lib "eagle-import") (part "resistor_R-US_R0402"))
    )
    (comp (ref "R47")
      (value "1K")
      (footprint "eagle-import:R0402")
      (libsource (lib "eagle-import") (part "resistor_R-US_R0402"))
    )
    (comp (ref "R48")
      (value "1K")
      (footprint "eagle-import:R0402")
      (libsource (lib "eagle-import") (part "resistor_R-US_R0402"))
    )
    (comp (ref "R49")
      (value "9K")
      (footprint "eagle-import:R0402")
      (libsource (lib "eagle-import") (part "resistor_R-US_R0402"))
    )
    (comp (ref "R50")
      (value "9K")
      (footprint "eagle-import:R0402")
      (libsource (lib "eagle-import") (part "resistor_R-US_R0402"))
    )
    (comp (ref "R51")
      (value "9K")
      (footprint "eagle-import:R0402")
      (libsource (lib "eagle-import") (part "resistor_R-US_R0402"))
    )
    (comp (ref "R52")
      (value "9K")
      (footprint "eagle-import:R0402")
      (libsource (lib "eagle-import") (part "resistor_R-US_R0402"))
    )
    (comp (ref "R53")
      (value "NM")
      (footprint "eagle-import:R0402")
      (libsource (lib "eagle-import") (part "resistor_R-US_R0402"))
    )
    (comp (ref "R54")
      (value "4K7")
      (footprint "eagle-import:R0402")
      (libsource (lib "eagle-import") (part "resistor_R-US_R0402"))
    )
    (comp (ref "R65")
      (value "10k")
      (footprint "eagle-import:R0402")
      (libsource (lib "eagle-import") (part "resistor_R-US_R0402"))
    )
    (comp (ref "R77")
      (value "NM")
      (footprint "eagle-import:R0805")
      (libsource (lib "eagle-import") (part "resistor_R-US_R0805"))
    )
    (comp (ref "R78")
      (value "NM")
      (footprint "eagle-import:R0805")
      (libsource (lib "eagle-import") (part "resistor_R-US_R0805"))
    )
    (comp (ref "U$4")
      (value "LDK220M33R")
      (footprint "eagle-import:SOT95P280X145-5N")
      (libsource (lib "eagle-import") (part "LDK220M33R"))
    )
    (comp (ref "U4")
      (value "STC4054GR")
      (footprint "eagle-import:SOT95P280X110-5N")
      (fields (field (name "MF") "STMicroelectronics"))
      (libsource (lib "eagle-import") (part "STC4054GR"))
    )
    (comp (ref "C18")
      (value "0.1uF")
      (footprint "eagle-import:C0402")
      (libsource (lib "eagle-import") (part "C-USC0402"))
    )
    (comp (ref "C65")
      (value "0.1uF")
      (footprint "eagle-import:C0402")
      (libsource (lib "eagle-import") (part "C-USC0402"))
    )
    (comp (ref "C66")
      (value "0.1uF")
      (footprint "eagle-import:C0402")
      (libsource (lib "eagle-import") (part "C-USC0402"))
    )
    (comp (ref "C67")
      (value "0.1uF")
      (footprint "eagle-import:C0402")
      (libsource (lib "eagle-import") (part "C-USC0402"))
    )
    (comp (ref "J1")
      (value "FOOT")
      (footprint "eagle-import:FOOT")
      (libsource (lib "eagle-import") (part "FOOT"))
    )
    (comp (ref "J3")
      (value "PINHD-1X2")
      (footprint "eagle-import:1X02")
      (libsource (lib "eagle-import") (part "PINHD-1X2"))
    )
    (comp (ref "J4")
      (value "PINHD-1X2")
      (footprint "eagle-import:1X02")
      (libsource (lib "eagle-import") (part "PINHD-1X2"))
    )
    (comp (ref "J6")
      (value "PINHD-1X2")
      (footprint "eagle-import:1X02")
      (libsource (lib "eagle-import") (part "PINHD-1X2"))
    )
    (comp (ref "J7")
      (value "PINHD-1X2")
      (footprint "eagle-import:1X02")
      (libsource (lib "eagle-import") (part "PINHD-1X2"))
    )
    (comp (ref "J9")
      (value "MA04-1")
      (footprint "eagle-import:MA04-1")
      (libsource (lib "eagle-import") (part "MA04-1"))
    )
    (comp (ref "J11")
      (value "MA04-1")
      (footprint "eagle-import:MA04-1")
      (libsource (lib "eagle-import") (part "MA04-1"))
    )
    (comp (ref "J12")
      (value "MA04-1")
      (footprint "eagle-import:MA04-1")
      (libsource (lib "eagle-import") (part "MA04-1"))
    )
    (comp (ref "J13")
      (value "MA04-1")
      (footprint "eagle-import:MA04-1")
      (libsource (lib "eagle-import") (part "MA04-1"))
    )
    (comp (ref "J15")
      (value "MA04-1")
      (footprint "eagle-import:MA04-1")
      (libsource (lib "eagle-import") (part "MA04-1"))
    )
    (comp (ref "J16")
      (value "FOOT")
      (footprint "eagle-import:FOOT")
      (libsource (lib "eagle-import") (part "FOOT"))
    )
    (comp (ref "Q8")
      (value "PMBT2222A")
      (footprint "eagle-import:SOT23-BEC")
      (fields (field (name "MF") "NXP Semiconductors"))
      (libsource (lib "eagle-import") (part "PMBT2222A"))
    )
    (comp (ref "Q9")
      (value "PMBT2222A")
      (footprint "eagle-import:SOT23-BEC")
      (fields (field (name "MF") "NXP Semiconductors"))
      (libsource (lib "eagle-import") (part "PMBT2222A"))
    )
    (comp (ref "Q10")
      (value "PMBT2222A")
      (footprint "eagle-import:SOT23-BEC")
      (fields (field (name "MF") "NXP Semiconductors"))
      (libsource (lib "eagle-import") (part "PMBT2222A"))
    )
    (comp (ref "Q11")
      (value "PMBT2222A")
      (footprint "eagle-import:SOT23-BEC")
      (fields (field (name "MF") "NXP Semiconductors"))
      (libsource (lib "eagle-import") (part "PMBT2222A"))
    )
    (comp (ref "R33")
      (value "9K")
      (footprint "eagle-import:R0402")
      (libsource (lib "eagle-import") (part "resistor_R-US_R0402"))
    )
    (comp (ref "R34")
      (value "9K")
      (footprint "eagle-import:R0402")
      (libsource (lib "eagle-import") (part "resistor_R-US_R0402"))
    )
    (comp (ref "R35")
      (value "9K")
      (footprint "eagle-import:R0402")
      (libsource (lib "eagle-import") (part "resistor_R-US_R0402"))
    )
    (comp (ref "R36")
      (value "9K")
      (footprint "eagle-import:R0402")
      (libsource (lib "eagle-import") (part "resistor_R-US_R0402"))
    )
    (comp (ref "R39")
      (value "1K")
      (footprint "eagle-import:R0402")
      (libsource (lib "eagle-import") (part "resistor_R-US_R0402"))
    )
    (comp (ref "R40")
      (value "1K")
      (footprint "eagle-import:R0402")
      (libsource (lib "eagle-import") (part "resistor_R-US_R0402"))
    )
    (comp (ref "R41")
      (value "1K")
      (footprint "eagle-import:R0402")
      (libsource (lib "eagle-import") (part "resistor_R-US_R0402"))
    )
    (comp (ref "R42")
      (value "1K")
      (footprint "eagle-import:R0402")
      (libsource (lib "eagle-import") (part "resistor_R-US_R0402"))
    )
    (comp (ref "R79")
      (value "4K7")
      (footprint "eagle-import:R0402")
      (libsource (lib "eagle-import") (part "resistor_R-US_R0402"))
    )
    (comp (ref "R80")
      (value "4K7")
      (footprint "eagle-import:R0402")
      (libsource (lib "eagle-import") (part "resistor_R-US_R0402"))
    )
    (comp (ref "R81")
      (value "4K7")
      (footprint "eagle-import:R0402")
      (libsource (lib "eagle-import") (part "resistor_R-US_R0402"))
    )
    (comp (ref "R82")
      (value "4K7")
      (footprint "eagle-import:R0402")
      (libsource (lib "eagle-import") (part "resistor_R-US_R0402"))
    )
    (comp (ref "C3")
      (value "VJ0805Y103MXXCW1BC")
      (footprint "eagle-import:C0805")
      (libsource (lib "eagle-import") (part "C-EUC0805"))
    )
    (comp (ref "C32")
      (value "0.1uF")
      (footprint "eagle-import:C0402")
      (libsource (lib "eagle-import") (part "C-EUC0402"))
    )
    (comp (ref "C33")
      (value "4.7uF 100V")
      (footprint "eagle-import:3.5X1.6X2.1(BXCXA)")
      (libsource (lib "eagle-import") (part "WCAP-PSLP_875105945001_6,3X7,7"))
    )
    (comp (ref "C34")
      (value "330pF")
      (footprint "eagle-import:C0805")
      (libsource (lib "eagle-import") (part "resistor_C-EUC0805"))
    )
    (comp (ref "C35")
      (value "0.1uF")
      (footprint "eagle-import:C0805")
      (libsource (lib "eagle-import") (part "resistor_C-EUC0805"))
    )
    (comp (ref "C36")
      (value "NM")
      (footprint "eagle-import:C0805")
      (libsource (lib "eagle-import") (part "resistor_C-EUC0805"))
    )
    (comp (ref "C37")
      (value "33uF 16V")
      (footprint "eagle-import:3.5X1.6X2.1(BXCXA)")
      (libsource (lib "eagle-import") (part "WCAP-ASLI_865080343005_6,3X5,5"))
    )
    (comp (ref "C54")
      (value "0.1uF")
      (footprint "eagle-import:C0402")
      (libsource (lib "eagle-import") (part "C-EUC0402"))
    )
    (comp (ref "C55")
      (value "0.1uF")
      (footprint "eagle-import:C0402")
      (libsource (lib "eagle-import") (part "C-EUC0402"))
    )
    (comp (ref "C56")
      (value "0.1uF")
      (footprint "eagle-import:C0402")
      (libsource (lib "eagle-import") (part "C-EUC0402"))
    )
    (comp (ref "C58")
      (value "0.1uF")
      (footprint "eagle-import:C0402")
      (libsource (lib "eagle-import") (part "C-EUC0402"))
    )
    (comp (ref "C60")
      (value "1uF")
      (footprint "eagle-import:C0603")
      (libsource (lib "eagle-import") (part "C-USC0603"))
    )
    (comp (ref "C61")
      (value "EEV-FK2A470Q")
      (footprint "eagle-import:SM_RADIAL_H13")
      (fields (field (name "MF") "Panasonic"))
      (libsource (lib "eagle-import") (part "EEV-FK2A470Q"))
    )
    (comp (ref "C62")
      (value "0.1uF")
      (footprint "eagle-import:C0402")
      (libsource (lib "eagle-import") (part "C-USC0402"))
    )
    (comp (ref "C63")
      (value "0.1uF")
      (footprint "eagle-import:C0402")
      (libsource (lib "eagle-import") (part "C-USC0402"))
    )
    (comp (ref "D7")
      (value "WE-TVSP_BI_1500W_824541331")
      (footprint "eagle-import:VARTVSP_SMC&SMD_DO-214AB")
      (libsource (lib "eagle-import") (part "WE-TVSP_BI_1500W_824541331"))
    )
    (comp (ref "D9")
      (value "SS110")
      (footprint "eagle-import:DO-214AC")
      (fields (field (name "MF") "ON Semiconductor") (field (name "MP") "S1M"))
      (libsource (lib "eagle-import") (part "S1M_S1M"))
    )
    (comp (ref "D15")
      (value "SS110")
      (footprint "eagle-import:DO-214AC")
      (fields (field (name "MF") "ON Semiconductor") (field (name "MP") "S1M"))
      (libsource (lib "eagle-import") (part "S1M_S1M"))
    )
    (comp (ref "D17")
      (value "TZMC3V3-GS08")
      (footprint "eagle-import:SOD80C")
      (libsource (lib "eagle-import") (part "ZENER-DIODESOD80C"))
    )
    (comp (ref "L2")
      (value "15uH")
      (footprint "eagle-import:WE-PD_1260_1245_1280_1210")
      (libsource (lib "eagle-import") (part "WE-PD_1260_744771115"))
    )
    (comp (ref "MOV1")
      (value "TMOV14R275E")
      (footprint "eagle-import:TMOV14R275E")
      (fields (field (name "MF") "Littelfuse Inc."))
      (libsource (lib "eagle-import") (part "TMOV14R275E"))
    )
    (comp (ref "Q2")
      (value "BC547")
      (footprint "eagle-import:SOT23")
      (libsource (lib "eagle-import") (part "NPN-TRANSISTOR_SOT23"))
    )
    (comp (ref "R14")
      (value "4K7")
      (footprint "eagle-import:R0402")
      (libsource (lib "eagle-import") (part "resistor_R-US_R0402"))
    )
    (comp (ref "R44")
      (value "10K")
      (footprint "eagle-import:R0805")
      (libsource (lib "eagle-import") (part "resistor_R-US_R0805"))
    )
    (comp (ref "R59")
      (value "17.4K")
      (footprint "eagle-import:R0805")
      (libsource (lib "eagle-import") (part "resistor_R-US_R0805"))
    )
    (comp (ref "R60")
      (value "100K")
      (footprint "eagle-import:R0805")
      (libsource (lib "eagle-import") (part "resistor_R-US_R0805"))
    )
    (comp (ref "R61")
      (value "200K")
      (footprint "eagle-import:R0805")
      (libsource (lib "eagle-import") (part "resistor_R-US_R0805"))
    )
    (comp (ref "R62")
      (value "40.2K")
      (footprint "eagle-import:R0805")
      (libsource (lib "eagle-import") (part "resistor_R-US_R0805"))
    )
    (comp (ref "R63")
      (value "210K")
      (footprint "eagle-import:R0805")
      (libsource (lib "eagle-import") (part "resistor_R-US_R0805"))
    )
    (comp (ref "R64")
      (value "47.5K")
      (footprint "eagle-import:R0805")
      (libsource (lib "eagle-import") (part "resistor_R-US_R0805"))
    )
    (comp (ref "R66")
      (value "4K7")
      (footprint "eagle-import:R0805")
      (libsource (lib "eagle-import") (part "resistor_R-US_R0805"))
    )
    (comp (ref "R68")
      (value "47K")
      (footprint "eagle-import:R0805")
      (libsource (lib "eagle-import") (part "resistor_R-US_R0805"))
    )
    (comp (ref "U7")
      (value "DRIVER-MAX3232ECDR(SOIC16)")
      (footprint "eagle-import:SOIC16-1.27-10X3.9MM")
      (fields (field (name "MF") "Texas Instruments") (field (name "MP") "MAX3232ECDR"))
      (libsource (lib "eagle-import") (part "DRIVER-MAX3232ECDR(SOIC16)"))
    )
    (comp (ref "U9")
      (value "MPU6050")
      (footprint "eagle-import:QFN50P400X400X95-25T265X275N")
      (libsource (lib "eagle-import") (part "MPU6050"))
    )
    (comp (ref "U10")
      (value "MP4559DN")
      (footprint "eagle-import:SOIC127P600X170-9N")
      (libsource (lib "eagle-import") (part "MP4559DN"))
    )
    (comp (ref "U11")
      (value "DF10S")
      (footprint "eagle-import:SOT508P985X260-4N")
      (fields (field (name "MF") "ON Semiconductor"))
      (libsource (lib "eagle-import") (part "DF10S"))
    )
    (comp (ref "C1")
      (value "22pF")
      (footprint "eagle-import:C0201")
      (libsource (lib "eagle-import") (part "C-EUC0201"))
    )
    (comp (ref "C2")
      (value "22pF")
      (footprint "eagle-import:C0201")
      (libsource (lib "eagle-import") (part "C-EUC0201"))
    )
    (comp (ref "C4")
      (value "10uF")
      (footprint "eagle-import:C0805")
      (libsource (lib "eagle-import") (part "C-USC0805"))
    )
    (comp (ref "C5")
      (value "1uF")
      (footprint "eagle-import:C0603")
      (libsource (lib "eagle-import") (part "C-USC0603"))
    )
    (comp (ref "C6")
      (value "0.1uF")
      (footprint "eagle-import:C0402")
      (libsource (lib "eagle-import") (part "C-USC0402"))
    )
    (comp (ref "C7")
      (value "0.1uF")
      (footprint "eagle-import:C0402")
      (libsource (lib "eagle-import") (part "C-USC0402"))
    )
    (comp (ref "C8")
      (value "0.1uF")
      (footprint "eagle-import:C0402")
      (libsource (lib "eagle-import") (part "C-USC0402"))
    )
    (comp (ref "C12")
      (value "0.1uF")
      (footprint "eagle-import:C0402")
      (libsource (lib "eagle-import") (part "C-USC0402"))
    )
    (comp (ref "C20")
      (value "33pF")
      (footprint "eagle-import:C0402")
      (libsource (lib "eagle-import") (part "C-EUC0402"))
    )
    (comp (ref "C21")
      (value "33pF")
      (footprint "eagle-import:C0402")
      (libsource (lib "eagle-import") (part "C-EUC0402"))
    )
    (comp (ref "C22")
      (value "33pF")
      (footprint "eagle-import:C0402")
      (libsource (lib "eagle-import") (part "C-EUC0402"))
    )
    (comp (ref "C23")
      (value "10pF")
      (footprint "eagle-import:C0402")
      (libsource (lib "eagle-import") (part "C-EUC0402"))
    )
    (comp (ref "C24")
      (value "10pF")
      (footprint "eagle-import:C0402")
      (libsource (lib "eagle-import") (part "C-EUC0402"))
    )
    (comp (ref "C25")
      (value "10pF")
      (footprint "eagle-import:C0402")
      (libsource (lib "eagle-import") (part "C-EUC0402"))
    )
    (comp (ref "C26")
      (value "10pF")
      (footprint "eagle-import:C0402")
      (libsource (lib "eagle-import") (part "C-EUC0402"))
    )
    (comp (ref "C27")
      (value "33pF")
      (footprint "eagle-import:C0402")
      (libsource (lib "eagle-import") (part "C-EUC0402"))
    )
    (comp (ref "C28")
      (value "10pF")
      (footprint "eagle-import:C0402")
      (libsource (lib "eagle-import") (part "C-EUC0402"))
    )
    (comp (ref "C29")
      (value "33pF")
      (footprint "eagle-import:C0402")
      (libsource (lib "eagle-import") (part "C-EUC0402"))
    )
    (comp (ref "C30")
      (value "10pF")
      (footprint "eagle-import:C0402")
      (libsource (lib "eagle-import") (part "C-EUC0402"))
    )
    (comp (ref "C31")
      (value "33pF")
      (footprint "eagle-import:C0402")
      (libsource (lib "eagle-import") (part "C-EUC0402"))
    )
    (comp (ref "C38")
      (value "10uF")
      (footprint "eagle-import:C0805")
      (libsource (lib "eagle-import") (part "resistor_C-USC0805"))
    )
    (comp (ref "C39")
      (value "0.1uF")
      (footprint "eagle-import:C0805")
      (libsource (lib "eagle-import") (part "resistor_C-EUC0805"))
    )
    (comp (ref "C40")
      (value "10uF")
      (footprint "eagle-import:C0805")
      (libsource (lib "eagle-import") (part "resistor_C-USC0805"))
    )
    (comp (ref "C57")
      (value "NM")
      (footprint "eagle-import:C0402")
      (libsource (lib "eagle-import") (part "C-USC0402"))
    )
    (comp (ref "D8")
      (value "S1M")
      (footprint "eagle-import:DO-214AC")
      (fields (field (name "MF") "ON Semiconductor"))
      (libsource (lib "eagle-import") (part "S1M_S1M"))
    )
    (comp (ref "D19")
      (value "TZMC3V3-GS08")
      (footprint "eagle-import:SOD80C")
      (libsource (lib "eagle-import") (part "ZENER-DIODESOD80C"))
    )
    (comp (ref "J5")
      (value "USB_MINI-B_SMT")
      (footprint "eagle-import:USB-MINIB")
      (libsource (lib "eagle-import") (part "USB_MINI-B_SMT"))
    )
    (comp (ref "J10")
      (value "MA04-1")
      (footprint "eagle-import:MA04-1")
      (libsource (lib "eagle-import") (part "MA04-1"))
    )
    (comp (ref "L1")
      (value "MF-MSMF050-2 500mA")
      (footprint "eagle-import:L1812")
      (libsource (lib "eagle-import") (part "L-EUL1812"))
    )
    (comp (ref "Q1")
      (value "8MHz")
      (footprint "eagle-import:QS")
      (libsource (lib "eagle-import") (part "XTAL/S"))
    )
    (comp (ref "R5")
      (value "10K")
      (footprint "eagle-import:R0402")
      (libsource (lib "eagle-import") (part "resistor_R-US_R0402"))
    )
    (comp (ref "R6")
      (value "10K")
      (footprint "eagle-import:R0402")
      (libsource (lib "eagle-import") (part "resistor_R-US_R0402"))
    )
    (comp (ref "R7")
      (value "22R")
      (footprint "eagle-import:R0402")
      (libsource (lib "eagle-import") (part "resistor_R-US_R0402"))
    )
    (comp (ref "R8")
      (value "22R")
      (footprint "eagle-import:R0402")
      (libsource (lib "eagle-import") (part "resistor_R-US_R0402"))
    )
    (comp (ref "R11")
      (value "1K5")
      (footprint "eagle-import:R0402")
      (libsource (lib "eagle-import") (part "resistor_R-US_R0402"))
    )
    (comp (ref "R12")
      (value "10K")
      (footprint "eagle-import:0603-RES")
      (libsource (lib "eagle-import") (part "RESISTOR0603-RES"))
    )
    (comp (ref "R13")
      (value "10K")
      (footprint "eagle-import:0603-RES")
      (libsource (lib "eagle-import") (part "RESISTOR0603-RES"))
    )
    (comp (ref "R15")
      (value "NM")
      (footprint "eagle-import:R0805")
      (libsource (lib "eagle-import") (part "resistor_R-US_R0805"))
    )
    (comp (ref "R24")
      (value "0R")
      (footprint "eagle-import:R0805")
      (libsource (lib "eagle-import") (part "resistor_R-US_R0805"))
    )
    (comp (ref "R58")
      (value "10K")
      (footprint "eagle-import:R0402")
      (libsource (lib "eagle-import") (part "resistor_R-US_R0402"))
    )
    (comp (ref "R67")
      (value "10K")
      (footprint "eagle-import:R0402")
      (libsource (lib "eagle-import") (part "resistor_R-US_R0402"))
    )
    (comp (ref "R76")
      (value "10K")
      (footprint "eagle-import:R0805")
      (libsource (lib "eagle-import") (part "resistor_R-US_R0805"))
    )
    (comp (ref "SW1")
      (value "5-1437565-0")
      (footprint "eagle-import:SW_5-1437565-0")
      (fields (field (name "MF") "TE Connectivity"))
      (libsource (lib "eagle-import") (part "5-1437565-0"))
    )
    (comp (ref "U2")
      (value "STM32F103C8T")
      (footprint "eagle-import:LQFP48")
      (libsource (lib "eagle-import") (part "STM32F103CT8"))
    )
  )
  (nets
    (net (code "1") (name "+5V") (class "Default")
      (node (ref "C37") (pin "1") (pinfunction "1_1") (pintype "passive"))
      (node (ref "L2") (pin "1") (pinfunction "1_1") (pintype "passive"))
      (node (ref "R24") (pin "2") (pinfunction "2_2") (pintype "passive"))
      (node (ref "R63") (pin "1") (pinfunction "1_1") (pintype "passive"))
    )
    (net (code "2") (name "+12V") (class "Default")
      (node (ref "C33") (pin "1") (pinfunction "1_1") (pintype "passive"))
      (node (ref "C61") (pin "1") (pinfunction "+_1") (pintype "passive"))
      (node (ref "D7") (pin "2") (pinfunction "2_2") (pintype "passive"))
      (node (ref "R20") (pin "2") (pinfunction "2_2") (pintype "passive"))
      (node (ref "R21") (pin "2") (pinfunction "2_2") (pintype "passive"))
      (node (ref "R22") (pin "2") (pinfunction "2_2") (pintype "passive"))
      (node (ref "R23") (pin "2") (pinfunction "2_2") (pintype "passive"))
      (node (ref "R60") (pin "2") (pinfunction "2_2") (pintype "passive"))
      (node (ref "R68") (pin "1") (pinfunction "1_1") (pintype "passive"))
      (node (ref "R77") (pin "2") (pinfunction "2_2") (pintype "passive"))
      (node (ref "U10") (pin "7") (pinfunction "VIN_7") (pintype "bidirectional"))
      (node (ref "U11") (pin "1") (pinfunction "OUT+_1") (pintype "output"))
    )
    (net (code "3") (name "1_WIRE") (class "Default")
      (node (ref "J1") (pin "1") (pinfunction "1_1") (pintype "passive"))
      (node (ref "U8") (pin "2") (pinfunction "1W_2") (pintype "open_collector"))
    )
    (net (code "4") (name "4.2V") (class "Default")
      (node (ref "C38") (pin "1") (pinfunction "1_1") (pintype "passive"))
      (node (ref "C39") (pin "1") (pinfunction "1_1") (pintype "passive"))
      (node (ref "C64") (pin "1") (pinfunction "+_1") (pintype "passive"))
      (node (ref "D4") (pin "C") (pinfunction "C_C") (pintype "passive"))
      (node (ref "D8") (pin "A") (pinfunction "A_A") (pintype "passive"))
      (node (ref "JP2") (pin "1") (pinfunction "1_1") (pintype "passive"))
      (node (ref "JP3") (pin "1") (pinfunction "1_1") (pintype "passive"))
      (node (ref "Q14") (pin "2") (pinfunction "S_2") (pintype "passive"))
      (node (ref "R44") (pin "1") (pinfunction "1_1") (pintype "passive"))
      (node (ref "R78") (pin "2") (pinfunction "2_2") (pintype "passive"))
    )
    (net (code "5") (name "5V") (class "Default")
      (node (ref "C68") (pin "1") (pinfunction "1_1") (pintype "passive"))
      (node (ref "C69") (pin "1") (pinfunction "1_1") (pintype "passive"))
      (node (ref "D4") (pin "A") (pinfunction "A_A") (pintype "passive"))
      (node (ref "J16") (pin "1") (pinfunction "1_1") (pintype "passive"))
      (node (ref "Q14") (pin "1") (pinfunction "G_1") (pintype "passive"))
      (node (ref "R15") (pin "1") (pinfunction "1_1") (pintype "passive"))
      (node (ref "R24") (pin "1") (pinfunction "1_1") (pintype "passive"))
      (node (ref "R43") (pin "2") (pinfunction "2_2") (pintype "passive"))
      (node (ref "U$3") (pin "6") (pinfunction "IN_6") (pintype "bidirectional"))
      (node (ref "U$4") (pin "1") (pinfunction "IN_1") (pintype "bidirectional"))
      (node (ref "U4") (pin "4") (pinfunction "VCC_4") (pintype "power_in"))
    )
    (net (code "6") (name "AI1") (class "Default")
      (node (ref "J12") (pin "1") (pinfunction "1_1") (pintype "passive"))
      (node (ref "R52") (pin "2") (pinfunction "2_2") (pintype "passive"))
    )
    (net (code "7") (name "AI2") (class "Default")
      (node (ref "J12") (pin "2") (pinfunction "2_2") (pintype "passive"))
      (node (ref "R51") (pin "2") (pinfunction "2_2") (pintype "passive"))
    )
    (net (code "8") (name "AI3") (class "Default")
      (node (ref "J12") (pin "3") (pinfunction "3_3") (pintype "passive"))
      (node (ref "R50") (pin "2") (pinfunction "2_2") (pintype "passive"))
      (node (ref "R77") (pin "1") (pinfunction "1_1") (pintype "passive"))
    )
    (net (code "9") (name "AI4") (class "Default")
      (node (ref "J12") (pin "4") (pinfunction "4_4") (pintype "passive"))
      (node (ref "R49") (pin "2") (pinfunction "2_2") (pintype "passive"))
      (node (ref "R78") (pin "1") (pinfunction "1_1") (pintype "passive"))
    )
    (net (code "10") (name "AIN0") (class "Default")
      (node (ref "C16") (pin "1") (pinfunction "1_1") (pintype "passive"))
      (node (ref "D10") (pin "C") (pinfunction "C_C") (pintype "passive"))
      (node (ref "R47") (pin "2") (pinfunction "2_2") (pintype "passive"))
      (node (ref "R51") (pin "1") (pinfunction "1_1") (pintype "passive"))
      (node (ref "U2") (pin "10") (pinfunction "PA0-WKUP_10") (pintype "bidirectional"))
    )
    (net (code "11") (name "AIN1") (class "Default")
      (node (ref "C15") (pin "1") (pinfunction "1_1") (pintype "passive"))
      (node (ref "D11") (pin "C") (pinfunction "C_C") (pintype "passive"))
      (node (ref "R46") (pin "2") (pinfunction "2_2") (pintype "passive"))
      (node (ref "R50") (pin "1") (pinfunction "1_1") (pintype "passive"))
      (node (ref "U2") (pin "11") (pinfunction "PA1_11") (pintype "bidirectional"))
    )
    (net (code "12") (name "AIN4") (class "Default")
      (node (ref "C14") (pin "1") (pinfunction "1_1") (pintype "passive"))
      (node (ref "D13") (pin "C") (pinfunction "C_C") (pintype "passive"))
      (node (ref "R45") (pin "2") (pinfunction "2_2") (pintype "passive"))
      (node (ref "R49") (pin "1") (pinfunction "1_1") (pintype "passive"))
      (node (ref "U2") (pin "14") (pinfunction "PA4_14") (pintype "bidirectional"))
    )
    (net (code "13") (name "AIN5") (class "Default")
      (node (ref "U2") (pin "15") (pinfunction "PA5_15") (pintype "bidirectional"))
    )
    (net (code "14") (name "AIN6") (class "Default")
      (node (ref "U2") (pin "16") (pinfunction "PA6_16") (pintype "bidirectional"))
    )
    (net (code "15") (name "CANH") (class "Default")
      (node (ref "J7") (pin "1") (pinfunction "1_1") (pintype "passive"))
      (node (ref "R3") (pin "2") (pinfunction "2_2") (pintype "passive"))
      (node (ref "R4") (pin "1") (pinfunction "1_1") (pintype "passive"))
      (node (ref "U1") (pin "7") (pinfunction "CANH_7") (pintype "bidirectional"))
    )
    (net (code "16") (name "CANL") (class "Default")
      (node (ref "J7") (pin "2") (pinfunction "2_2") (pintype "passive"))
      (node (ref "R2") (pin "2") (pinfunction "2_2") (pintype "passive"))
      (node (ref "R4") (pin "2") (pinfunction "2_2") (pintype "passive"))
      (node (ref "U1") (pin "6") (pinfunction "CANL_6") (pintype "bidirectional"))
    )
    (net (code "17") (name "CANRX") (class "Default")
      (node (ref "U1") (pin "4") (pinfunction "RXD_4") (pintype "bidirectional"))
      (node (ref "U2") (pin "45") (pinfunction "PB8_45") (pintype "bidirectional"))
    )
    (net (code "18") (name "CANTX") (class "Default")
      (node (ref "U1") (pin "1") (pinfunction "TXD_1") (pintype "bidirectional"))
      (node (ref "U2") (pin "46") (pinfunction "PB9_46") (pintype "bidirectional"))
    )
    (net (code "19") (name "CS_SF") (class "Default")
      (node (ref "U5") (pin "30") (pinfunction "PCM_CLK_30") (pintype "bidirectional"))
      (node (ref "U6") (pin "1") (pinfunction "~{CS}_1") (pintype "input"))
    )
    (net (code "20") (name "DI1") (class "Default")
      (node (ref "Q8") (pin "C") (pinfunction "C_C") (pintype "passive"))
      (node (ref "R79") (pin "2") (pinfunction "2_2") (pintype "passive"))
      (node (ref "U2") (pin "38") (pinfunction "PA15_38") (pintype "bidirectional"))
    )
    (net (code "21") (name "DI2") (class "Default")
      (node (ref "Q10") (pin "C") (pinfunction "C_C") (pintype "passive"))
      (node (ref "R80") (pin "2") (pinfunction "2_2") (pintype "passive"))
      (node (ref "U2") (pin "40") (pinfunction "PB4_40") (pintype "bidirectional"))
    )
    (net (code "22") (name "DI3") (class "Default")
      (node (ref "Q11") (pin "C") (pinfunction "C_C") (pintype "passive"))
      (node (ref "R81") (pin "2") (pinfunction "2_2") (pintype "passive"))
      (node (ref "U2") (pin "41") (pinfunction "PB5_41") (pintype "bidirectional"))
    )
    (net (code "23") (name "DI4") (class "Default")
      (node (ref "U2") (pin "2") (pinfunction "PC13_2") (pintype "bidirectional"))
    )
    (net (code "24") (name "DI6") (class "Default")
      (node (ref "Q9") (pin "C") (pinfunction "C_C") (pintype "passive"))
      (node (ref "R82") (pin "2") (pinfunction "2_2") (pintype "passive"))
      (node (ref "U2") (pin "4") (pinfunction "PC15_4") (pintype "bidirectional"))
    )
    (net (code "25") (name "DIV1") (class "Default")
      (node (ref "C18") (pin "1") (pinfunction "1_1") (pintype "passive"))
      (node (ref "J11") (pin "1") (pinfunction "1_1") (pintype "passive"))
      (node (ref "R33") (pin "2") (pinfunction "2_2") (pintype "passive"))
    )
    (net (code "26") (name "DIV2") (class "Default")
      (node (ref "C65") (pin "1") (pinfunction "1_1") (pintype "passive"))
      (node (ref "J11") (pin "2") (pinfunction "2_2") (pintype "passive"))
      (node (ref "R34") (pin "2") (pinfunction "2_2") (pintype "passive"))
    )
    (net (code "27") (name "DIV3") (class "Default")
      (node (ref "C66") (pin "1") (pinfunction "1_1") (pintype "passive"))
      (node (ref "J11") (pin "3") (pinfunction "3_3") (pintype "passive"))
      (node (ref "R35") (pin "2") (pinfunction "2_2") (pintype "passive"))
    )
    (net (code "28") (name "DIV4") (class "Default")
      (node (ref "C67") (pin "1") (pinfunction "1_1") (pintype "passive"))
      (node (ref "J11") (pin "4") (pinfunction "4_4") (pintype "passive"))
      (node (ref "R36") (pin "2") (pinfunction "2_2") (pintype "passive"))
    )
    (net (code "29") (name "DO1") (class "Default")
      (node (ref "R19") (pin "1") (pinfunction "1_1") (pintype "passive"))
      (node (ref "U2") (pin "18") (pinfunction "PB0_18") (pintype "bidirectional"))
    )
    (net (code "30") (name "DO2") (class "Default")
      (node (ref "R18") (pin "1") (pinfunction "1_1") (pintype "passive"))
      (node (ref "U2") (pin "19") (pinfunction "PB1_19") (pintype "bidirectional"))
    )
    (net (code "31") (name "DO3") (class "Default")
      (node (ref "R17") (pin "1") (pinfunction "1_1") (pintype "passive"))
      (node (ref "U2") (pin "25") (pinfunction "PB12_25") (pintype "bidirectional"))
    )
    (net (code "32") (name "DO4") (class "Default")
      (node (ref "R16") (pin "1") (pinfunction "1_1") (pintype "passive"))
      (node (ref "U2") (pin "26") (pinfunction "PB13_26") (pintype "bidirectional"))
    )
    (net (code "33") (name "DOV1") (class "Default")
      (node (ref "J13") (pin "1") (pinfunction "1_1") (pintype "passive"))
      (node (ref "Q6") (pin "C") (pinfunction "C_C") (pintype "passive"))
      (node (ref "R20") (pin "1") (pinfunction "1_1") (pintype "passive"))
    )
    (net (code "34") (name "DOV2") (class "Default")
      (node (ref "J13") (pin "2") (pinfunction "2_2") (pintype "passive"))
      (node (ref "Q7") (pin "C") (pinfunction "C_C") (pintype "passive"))
      (node (ref "R21") (pin "1") (pinfunction "1_1") (pintype "passive"))
    )
    (net (code "35") (name "DOV3") (class "Default")
      (node (ref "J13") (pin "3") (pinfunction "3_3") (pintype "passive"))
      (node (ref "Q3") (pin "C") (pinfunction "C_C") (pintype "passive"))
      (node (ref "R22") (pin "1") (pinfunction "1_1") (pintype "passive"))
    )
    (net (code "36") (name "DOV4") (class "Default")
      (node (ref "J13") (pin "4") (pinfunction "4_4") (pintype "passive"))
      (node (ref "Q4") (pin "C") (pinfunction "C_C") (pintype "passive"))
      (node (ref "R23") (pin "1") (pinfunction "1_1") (pintype "passive"))
    )
    (net (code "37") (name "DO_CTRL") (class "Default")
      (node (ref "U2") (pin "29") (pinfunction "PA8_29") (pintype "bidirectional"))
    )
    (net (code "38") (name "GND") (class "Default")
      (node (ref "C1") (pin "1") (pinfunction "1_1") (pintype "passive"))
      (node (ref "C10") (pin "2") (pinfunction "2_2") (pintype "passive"))
      (node (ref "C11") (pin "2") (pinfunction "2_2") (pintype "passive"))
      (node (ref "C12") (pin "2") (pinfunction "2_2") (pintype "passive"))
      (node (ref "C13") (pin "2") (pinfunction "2_2") (pintype "passive"))
      (node (ref "C14") (pin "2") (pinfunction "2_2") (pintype "passive"))
      (node (ref "C15") (pin "2") (pinfunction "2_2") (pintype "passive"))
      (node (ref "C16") (pin "2") (pinfunction "2_2") (pintype "passive"))
      (node (ref "C17") (pin "2") (pinfunction "2_2") (pintype "passive"))
      (node (ref "C18") (pin "2") (pinfunction "2_2") (pintype "passive"))
      (node (ref "C19") (pin "2") (pinfunction "2_2") (pintype "passive"))
      (node (ref "C2") (pin "1") (pinfunction "1_1") (pintype "passive"))
      (node (ref "C20") (pin "1") (pinfunction "1_1") (pintype "passive"))
      (node (ref "C22") (pin "2") (pinfunction "2_2") (pintype "passive"))
      (node (ref "C23") (pin "1") (pinfunction "1_1") (pintype "passive"))
      (node (ref "C25") (pin "2") (pinfunction "2_2") (pintype "passive"))
      (node (ref "C26") (pin "1") (pinfunction "1_1") (pintype "passive"))
      (node (ref "C27") (pin "1") (pinfunction "1_1") (pintype "passive"))
      (node (ref "C3") (pin "2") (pinfunction "2_2") (pintype "passive"))
      (node (ref "C30") (pin "2") (pinfunction "2_2") (pintype "passive"))
      (node (ref "C31") (pin "2") (pinfunction "2_2") (pintype "passive"))
      (node (ref "C33") (pin "2") (pinfunction "2_2") (pintype "passive"))
      (node (ref "C36") (pin "2") (pinfunction "2_2") (pintype "passive"))
      (node (ref "C37") (pin "2") (pinfunction "2_2") (pintype "passive"))
      (node (ref "C38") (pin "2") (pinfunction "2_2") (pintype "passive"))
      (node (ref "C39") (pin "2") (pinfunction "2_2") (pintype "passive"))
      (node (ref "C4") (pin "2") (pinfunction "2_2") (pintype "passive"))
      (node (ref "C40") (pin "2") (pinfunction "2_2") (pintype "passive"))
      (node (ref "C41") (pin "2") (pinfunction "2_2") (pintype "passive"))
      (node (ref "C42") (pin "2") (pinfunction "2_2") (pintype "passive"))
      (node (ref "C43") (pin "2") (pinfunction "2_2") (pintype "passive"))
      (node (ref "C44") (pin "2") (pinfunction "2_2") (pintype "passive"))
      (node (ref "C45") (pin "2") (pinfunction "2_2") (pintype "passive"))
      (node (ref "C46") (pin "2") (pinfunction "2_2") (pintype "passive"))
      (node (ref "C48") (pin "2") (pinfunction "2_2") (pintype "passive"))
      (node (ref "C49") (pin "2") (pinfunction "2_2") (pintype "passive"))
      (node (ref "C5") (pin "2") (pinfunction "2_2") (pintype "passive"))
      (node (ref "C50") (pin "2") (pinfunction "2_2") (pintype "passive"))
      (node (ref "C51") (pin "-") (pinfunction "-_-") (pintype "passive"))
      (node (ref "C52") (pin "2") (pinfunction "2_2") (pintype "passive"))
      (node (ref "C53") (pin "2") (pinfunction "2_2") (pintype "passive"))
      (node (ref "C55") (pin "2") (pinfunction "2_2") (pintype "passive"))
      (node (ref "C57") (pin "2") (pinfunction "2_2") (pintype "passive"))
      (node (ref "C58") (pin "2") (pinfunction "2_2") (pintype "passive"))
      (node (ref "C59") (pin "2") (pinfunction "2_2") (pintype "passive"))
      (node (ref "C6") (pin "2") (pinfunction "2_2") (pintype "passive"))
      (node (ref "C60") (pin "2") (pinfunction "2_2") (pintype "passive"))
      (node (ref "C61") (pin "2") (pinfunction "-_2") (pintype "passive"))
      (node (ref "C62") (pin "2") (pinfunction "2_2") (pintype "passive"))
      (node (ref "C63") (pin "2") (pinfunction "2_2") (pintype "passive"))
      (node (ref "C64") (pin "2") (pinfunction "-_2") (pintype "passive"))
      (node (ref "C65") (pin "2") (pinfunction "2_2") (pintype "passive"))
      (node (ref "C66") (pin "2") (pinfunction "2_2") (pintype "passive"))
      (node (ref "C67") (pin "2") (pinfunction "2_2") (pintype "passive"))
      (node (ref "C68") (pin "2") (pinfunction "2_2") (pintype "passive"))
      (node (ref "C69") (pin "2") (pinfunction "2_2") (pintype "passive"))
      (node (ref "C7") (pin "2") (pinfunction "2_2") (pintype "passive"))
      (node (ref "C70") (pin "2") (pinfunction "2_2") (pintype "passive"))
      (node (ref "C71") (pin "2") (pinfunction "2_2") (pintype "passive"))
      (node (ref "C8") (pin "2") (pinfunction "2_2") (pintype "passive"))
      (node (ref "C9") (pin "2") (pinfunction "2_2") (pintype "passive"))
      (node (ref "D10") (pin "A") (pinfunction "A_A") (pintype "passive"))
      (node (ref "D11") (pin "A") (pinfunction "A_A") (pintype "passive"))
      (node (ref "D12") (pin "A") (pinfunction "A_A") (pintype "passive"))
      (node (ref "D13") (pin "A") (pinfunction "A_A") (pintype "passive"))
      (node (ref "D15") (pin "A") (pinfunction "A_A") (pintype "passive"))
      (node (ref "D17") (pin "A") (pinfunction "A_A") (pintype "passive"))
      (node (ref "D19") (pin "A") (pinfunction "A_A") (pintype "passive"))
      (node (ref "D7") (pin "1") (pinfunction "1_1") (pintype "passive"))
      (node (ref "D9") (pin "A") (pinfunction "A_A") (pintype "passive"))
      (node (ref "J10") (pin "1") (pinfunction "1_1") (pintype "passive"))
      (node (ref "J14") (pin "2") (pinfunction "S_2") (pintype "passive"))
      (node (ref "J2") (pin "GND@0") (pinfunction "2_GND@0") (pintype "passive"))
      (node (ref "J5") (pin "GND") (pinfunction "GND_GND") (pintype "power_in"))
      (node (ref "J5") (pin "ID") (pinfunction "ID_ID") (pintype "bidirectional"))
      (node (ref "J5") (pin "S1") (pinfunction "SHIELD_S1") (pintype "bidirectional"))
      (node (ref "J5") (pin "S2") (pinfunction "SHIELD_S2") (pintype "bidirectional"))
      (node (ref "J5") (pin "S3") (pinfunction "SHIELD_S3") (pintype "bidirectional"))
      (node (ref "J5") (pin "S4") (pinfunction "SHIELD_S4") (pintype "bidirectional"))
      (node (ref "J8") (pin "3") (pinfunction "3_3") (pintype "passive"))
      (node (ref "J9") (pin "1") (pinfunction "1_1") (pintype "passive"))
      (node (ref "J9") (pin "2") (pinfunction "2_2") (pintype "passive"))
      (node (ref "J9") (pin "3") (pinfunction "3_3") (pintype "passive"))
      (node (ref "J9") (pin "4") (pinfunction "4_4") (pintype "passive"))
      (node (ref "Q10") (pin "E") (pinfunction "E_E") (pintype "passive"))
      (node (ref "Q11") (pin "E") (pinfunction "E_E") (pintype "passive"))
      (node (ref "Q12") (pin "2") (pinfunction "E_2") (pintype "passive"))
      (node (ref "Q13") (pin "2") (pinfunction "E_2") (pintype "passive"))
      (node (ref "Q2") (pin "2") (pinfunction "E_2") (pintype "passive"))
      (node (ref "Q3") (pin "E") (pinfunction "E_E") (pintype "passive"))
      (node (ref "Q4") (pin "E") (pinfunction "E_E") (pintype "passive"))
      (node (ref "Q5") (pin "2") (pinfunction "E_2") (pintype "passive"))
      (node (ref "Q6") (pin "E") (pinfunction "E_E") (pintype "passive"))
      (node (ref "Q7") (pin "E") (pinfunction "E_E") (pintype "passive"))
      (node (ref "Q8") (pin "E") (pinfunction "E_E") (pintype "passive"))
      (node (ref "Q9") (pin "E") (pinfunction "E_E") (pintype "passive"))
      (node (ref "R1") (pin "1") (pinfunction "1_1") (pintype "passive"))
      (node (ref "R14") (pin "2") (pinfunction "2_2") (pintype "passive"))
      (node (ref "R25") (pin "2") (pinfunction "2_2") (pintype "passive"))
      (node (ref "R30") (pin "2") (pinfunction "2_2") (pintype "passive"))
      (node (ref "R39") (pin "1") (pinfunction "1_1") (pintype "passive"))
      (node (ref "R40") (pin "1") (pinfunction "1_1") (pintype "passive"))
      (node (ref "R41") (pin "1") (pinfunction "1_1") (pintype "passive"))
      (node (ref "R42") (pin "1") (pinfunction "1_1") (pintype "passive"))
      (node (ref "R45") (pin "1") (pinfunction "1_1") (pintype "passive"))
      (node (ref "R46") (pin "1") (pinfunction "1_1") (pintype "passive"))
      (node (ref "R47") (pin "1") (pinfunction "1_1") (pintype "passive"))
      (node (ref "R48") (pin "1") (pinfunction "1_1") (pintype "passive"))
      (node (ref "R5") (pin "1") (pinfunction "1_1") (pintype "passive"))
      (node (ref "R53") (pin "1") (pinfunction "1_1") (pintype "passive"))
      (node (ref "R56") (pin "2") (pinfunction "2_2") (pintype "passive"))
      (node (ref "R59") (pin "2") (pinfunction "2_2") (pintype "passive"))
      (node (ref "R6") (pin "2") (pinfunction "2_2") (pintype "passive"))
      (node (ref "R61") (pin "2") (pinfunction "2_2") (pintype "passive"))
      (node (ref "R62") (pin "1") (pinfunction "1_1") (pintype "passive"))
      (node (ref "R64") (pin "1") (pinfunction "1_1") (pintype "passive"))
      (node (ref "R65") (pin "2") (pinfunction "2_2") (pintype "passive"))
      (node (ref "R66") (pin "1") (pinfunction "1_1") (pintype "passive"))
      (node (ref "R69") (pin "1") (pinfunction "1_1") (pintype "passive"))
      (node (ref "R70") (pin "1") (pinfunction "1_1") (pintype "passive"))
      (node (ref "R84") (pin "2") (pinfunction "2_2") (pintype "passive"))
      (node (ref "R87") (pin "2") (pinfunction "2_2") (pintype "passive"))
      (node (ref "SW1") (pin "3") (pinfunction "1_3") (pintype "passive"))
      (node (ref "SW1") (pin "4") (pinfunction "1_4") (pintype "passive"))
      (node (ref "U$1") (pin "12") (pinfunction "GND_12") (pintype "bidirectional"))
      (node (ref "U$1") (pin "3") (pinfunction "GND_3") (pintype "bidirectional"))
      (node (ref "U$3") (pin "3") (pinfunction "GND_3") (pintype "bidirectional"))
      (node (ref "U$3") (pin "7") (pinfunction "GND_7") (pintype "bidirectional"))
      (node (ref "U$4") (pin "2") (pinfunction "GND_2") (pintype "bidirectional"))
      (node (ref "U1") (pin "2") (pinfunction "VSS_2") (pintype "bidirectional"))
      (node (ref "U10") (pin "5") (pinfunction "GND_5") (pintype "bidirectional"))
      (node (ref "U10") (pin "9") (pinfunction "ES_9") (pintype "power_in"))
      (node (ref "U11") (pin "2") (pinfunction "OUT-_2") (pintype "output"))
      (node (ref "U12") (pin "2") (pinfunction "GND_2") (pintype "bidirectional"))
      (node (ref "U2") (pin "8") (pinfunction "VSSA_8") (pintype "power_in"))
      (node (ref "U4") (pin "2") (pinfunction "GND_2") (pintype "power_in"))
      (node (ref "U5") (pin "1") (pinfunction "AGND_1") (pintype "bidirectional"))
      (node (ref "U5") (pin "27") (pinfunction "GND_27") (pintype "bidirectional"))
      (node (ref "U5") (pin "34") (pinfunction "GND_34") (pintype "bidirectional"))
      (node (ref "U5") (pin "36") (pinfunction "GND_36") (pintype "bidirectional"))
      (node (ref "U5") (pin "37") (pinfunction "GND_37") (pintype "bidirectional"))
      (node (ref "U5") (pin "40") (pinfunction "GND_40") (pintype "bidirectional"))
      (node (ref "U5") (pin "41") (pinfunction "GND_41") (pintype "bidirectional"))
      (node (ref "U6") (pin "4") (pinfunction "GND_4") (pintype "power_in"))
      (node (ref "U6") (pin "9") (pinfunction "EXP_9") (pintype "passive"))
      (node (ref "U7") (pin "15") (pinfunction "GND_15") (pintype "power_in"))
      (node (ref "U8") (pin "1") (pinfunction "GND_1") (pintype "power_in"))
      (node (ref "U9") (pin "1") (pinfunction "CLKIN_1") (pintype "input"))
      (node (ref "U9") (pin "18") (pinfunction "GND_18") (pintype "power_in"))
      (node (ref "U9") (pin "25") (pinfunction "GND_25") (pintype "power_in"))
    )
    (net (code "39") (name "GPSL") (class "Default")
      (node (ref "U$4") (pin "3") (pinfunction "EN_3") (pintype "bidirectional"))
      (node (ref "U2") (pin "27") (pinfunction "PB14_27") (pintype "bidirectional"))
    )
    (net (code "40") (name "GPSP") (class "Default")
      (node (ref "C41") (pin "1") (pinfunction "1_1") (pintype "passive"))
      (node (ref "C59") (pin "1") (pinfunction "1_1") (pintype "passive"))
      (node (ref "C70") (pin "1") (pinfunction "1_1") (pintype "passive"))
      (node (ref "JP1") (pin "2") (pinfunction "2_2") (pintype "passive"))
      (node (ref "R29") (pin "2") (pinfunction "2_2") (pintype "passive"))
      (node (ref "U$1") (pin "4") (pinfunction "VCC_4") (pintype "bidirectional"))
      (node (ref "U$4") (pin "5") (pinfunction "OUT_5") (pintype "bidirectional"))
    )
    (net (code "41") (name "GPS_RX") (class "Default")
      (node (ref "R27") (pin "1") (pinfunction "1_1") (pintype "passive"))
      (node (ref "U5") (pin "39") (pinfunction "DBG_TXD_39") (pintype "bidirectional"))
    )
    (net (code "42") (name "GPS_STAT") (class "Default")
      (node (ref "LED3") (pin "A") (pinfunction "A_A") (pintype "passive"))
      (node (ref "U5") (pin "22") (pinfunction "CTS_22") (pintype "bidirectional"))
    )
    (net (code "43") (name "GPS_TX") (class "Default")
      (node (ref "JP4") (pin "1") (pinfunction "1_1") (pintype "passive"))
      (node (ref "R83") (pin "1") (pinfunction "1_1") (pintype "passive"))
      (node (ref "U5") (pin "38") (pinfunction "DBG_RXD_38") (pintype "bidirectional"))
    )
    (net (code "44") (name "GSML") (class "Default")
      (node (ref "U$3") (pin "5") (pinfunction "EN_5") (pintype "bidirectional"))
      (node (ref "U2") (pin "28") (pinfunction "PB15_28") (pintype "bidirectional"))
    )
    (net (code "45") (name "GSMP") (class "Default")
      (node (ref "C13") (pin "1") (pinfunction "1_1") (pintype "passive"))
      (node (ref "C42") (pin "1") (pinfunction "1_1") (pintype "passive"))
      (node (ref "C43") (pin "1") (pinfunction "1_1") (pintype "passive"))
      (node (ref "C44") (pin "1") (pinfunction "1_1") (pintype "passive"))
      (node (ref "C51") (pin "+") (pinfunction "+_+") (pintype "passive"))
      (node (ref "C71") (pin "1") (pinfunction "1_1") (pintype "passive"))
      (node (ref "D18") (pin "A") (pinfunction "A_A") (pintype "passive"))
      (node (ref "D2") (pin "A") (pinfunction "A_A") (pintype "passive"))
      (node (ref "JP2") (pin "2") (pinfunction "2_2") (pintype "passive"))
      (node (ref "LED1") (pin "A") (pinfunction "A_A") (pintype "passive"))
      (node (ref "R57") (pin "1") (pinfunction "1_1") (pintype "passive"))
      (node (ref "R71") (pin "2") (pinfunction "2_2") (pintype "passive"))
      (node (ref "R73") (pin "2") (pinfunction "2_2") (pintype "passive"))
      (node (ref "R86") (pin "1") (pinfunction "1_1") (pintype "passive"))
      (node (ref "U$3") (pin "1") (pinfunction "OUT_1") (pintype "bidirectional"))
    )
    (net (code "46") (name "GSM_AI0") (class "Default")
      (node (ref "C19") (pin "1") (pinfunction "1_1") (pintype "passive"))
      (node (ref "R54") (pin "1") (pinfunction "1_1") (pintype "passive"))
      (node (ref "U5") (pin "9") (pinfunction "ADC0_9") (pintype "bidirectional"))
    )
    (net (code "47") (name "GSM_ANT") (class "Default")
      (node (ref "C52") (pin "1") (pinfunction "1_1") (pintype "passive"))
      (node (ref "R38") (pin "1") (pinfunction "1_1") (pintype "passive"))
      (node (ref "U5") (pin "35") (pinfunction "RF_ANT_35") (pintype "bidirectional"))
    )
    (net (code "48") (name "GSM_PWR") (class "Default")
      (node (ref "R55") (pin "2") (pinfunction "2_2") (pintype "passive"))
      (node (ref "U2") (pin "3") (pinfunction "PC14_3") (pintype "bidirectional"))
    )
    (net (code "49") (name "GSM_RX1") (class "Default")
      (node (ref "U2") (pin "30") (pinfunction "PA9_30") (pintype "bidirectional"))
      (node (ref "U5") (pin "28") (pinfunction "RXD_AUX_28") (pintype "bidirectional"))
    )
    (net (code "50") (name "GSM_STAT") (class "Default")
      (node (ref "LED2") (pin "A") (pinfunction "A_A") (pintype "passive"))
      (node (ref "U5") (pin "16") (pinfunction "NETLIGHT_16") (pintype "bidirectional"))
    )
    (net (code "51") (name "GSM_TX1") (class "Default")
      (node (ref "U2") (pin "31") (pinfunction "PA10_31") (pintype "bidirectional"))
      (node (ref "U5") (pin "29") (pinfunction "TXD_AUX_29") (pintype "bidirectional"))
    )
    (net (code "52") (name "MIC1N") (class "Default")
      (node (ref "C28") (pin "2") (pinfunction "2_2") (pintype "passive"))
      (node (ref "C29") (pin "2") (pinfunction "2_2") (pintype "passive"))
      (node (ref "C30") (pin "1") (pinfunction "1_1") (pintype "passive"))
      (node (ref "C31") (pin "1") (pinfunction "1_1") (pintype "passive"))
      (node (ref "J15") (pin "2") (pinfunction "2_2") (pintype "passive"))
      (node (ref "U5") (pin "4") (pinfunction "MICN_4") (pintype "bidirectional"))
    )
    (net (code "53") (name "MIC1P") (class "Default")
      (node (ref "C26") (pin "2") (pinfunction "2_2") (pintype "passive"))
      (node (ref "C27") (pin "2") (pinfunction "2_2") (pintype "passive"))
      (node (ref "C28") (pin "1") (pinfunction "1_1") (pintype "passive"))
      (node (ref "C29") (pin "1") (pinfunction "1_1") (pintype "passive"))
      (node (ref "J15") (pin "1") (pinfunction "1_1") (pintype "passive"))
      (node (ref "U5") (pin "3") (pinfunction "MICP_3") (pintype "bidirectional"))
    )
    (net (code "54") (name "MISO_SF") (class "Default")
      (node (ref "U5") (pin "31") (pinfunction "PCM_SYNC_31") (pintype "bidirectional"))
      (node (ref "U6") (pin "2") (pinfunction "DO(IO1)_2") (pintype "bidirectional"))
    )
    (net (code "55") (name "MOSI_SF") (class "Default")
      (node (ref "U5") (pin "33") (pinfunction "PCM_OUT_33") (pintype "bidirectional"))
      (node (ref "U6") (pin "5") (pinfunction "DI(IO0)_5") (pintype "bidirectional"))
    )
    (net (code "56") (name "MPU_INT") (class "Default")
      (node (ref "U2") (pin "39") (pinfunction "PB3_39") (pintype "bidirectional"))
      (node (ref "U9") (pin "12") (pinfunction "INT_12") (pintype "open_collector"))
    )
    (net (code "57") (name "Net-(C10-Pad1)") (class "Default")
      (node (ref "C10") (pin "1") (pinfunction "1_1") (pintype "passive"))
      (node (ref "R2") (pin "1") (pinfunction "1_1") (pintype "passive"))
    )
    (net (code "58") (name "Net-(C11-Pad1)") (class "Default")
      (node (ref "C11") (pin "1") (pinfunction "1_1") (pintype "passive"))
      (node (ref "R3") (pin "1") (pinfunction "1_1") (pintype "passive"))
    )
    (net (code "59") (name "Net-(C17-Pad1)") (class "Default")
      (node (ref "C17") (pin "1") (pinfunction "1_1") (pintype "passive"))
      (node (ref "D12") (pin "C") (pinfunction "C_C") (pintype "passive"))
      (node (ref "R48") (pin "2") (pinfunction "2_2") (pintype "passive"))
      (node (ref "R52") (pin "1") (pinfunction "1_1") (pintype "passive"))
      (node (ref "R53") (pin "2") (pinfunction "2_2") (pintype "passive"))
      (node (ref "R54") (pin "2") (pinfunction "2_2") (pintype "passive"))
    )
    (net (code "60") (name "Net-(C34-Pad2)") (class "Default")
      (node (ref "C34") (pin "2") (pinfunction "2_2") (pintype "passive"))
      (node (ref "R64") (pin "2") (pinfunction "2_2") (pintype "passive"))
    )
    (net (code "61") (name "Net-(C53-Pad1)") (class "Default")
      (node (ref "C53") (pin "1") (pinfunction "1_1") (pintype "passive"))
      (node (ref "R28") (pin "1") (pinfunction "1_1") (pintype "passive"))
      (node (ref "R38") (pin "2") (pinfunction "2_2") (pintype "passive"))
    )
    (net (code "62") (name "Net-(D2-PadC)") (class "Default")
      (node (ref "D2") (pin "C") (pinfunction "C_C") (pintype "passive"))
      (node (ref "U5") (pin "42") (pinfunction "VBAT_42") (pintype "bidirectional"))
      (node (ref "U5") (pin "43") (pinfunction "VBAT_43") (pintype "bidirectional"))
    )
    (net (code "63") (name "Net-(D3-PadC)") (class "Default")
      (node (ref "D3") (pin "C") (pinfunction "C_C") (pintype "passive"))
      (node (ref "R27") (pin "2") (pinfunction "2_2") (pintype "passive"))
    )
    (net (code "64") (name "Net-(D8-PadC)") (class "Default")
      (node (ref "D8") (pin "C") (pinfunction "C_C") (pintype "passive"))
      (node (ref "R76") (pin "1") (pinfunction "1_1") (pintype "passive"))
    )
    (net (code "65") (name "Net-(J2-1)") (class "Default")
      (node (ref "J2") (pin "S") (pinfunction "1_S") (pintype "passive"))
      (node (ref "R28") (pin "2") (pinfunction "2_2") (pintype "passive"))
    )
    (net (code "66") (name "Net-(J5-PadD+)") (class "Default")
      (node (ref "J5") (pin "D+") (pinfunction "D+_D+") (pintype "bidirectional"))
      (node (ref "R8") (pin "2") (pinfunction "2_2") (pintype "passive"))
    )
    (net (code "67") (name "Net-(J5-PadD-)") (class "Default")
      (node (ref "J5") (pin "D-") (pinfunction "D-_D-") (pintype "bidirectional"))
      (node (ref "R7") (pin "2") (pinfunction "2_2") (pintype "passive"))
    )
    (net (code "68") (name "Net-(J5-PadVBUS)") (class "Default")
      (node (ref "J5") (pin "VBUS") (pinfunction "VBUS_VBUS") (pintype "power_in"))
      (node (ref "L1") (pin "1") (pinfunction "1_1") (pintype "passive"))
    )
    (net (code "69") (name "Net-(J14A-S)") (class "Default")
      (node (ref "J14") (pin "1") (pinfunction "S_1") (pintype "passive"))
      (node (ref "JP3") (pin "2") (pinfunction "2_2") (pintype "passive"))
      (node (ref "Q14") (pin "3") (pinfunction "D_3") (pintype "passive"))
      (node (ref "U4") (pin "3") (pinfunction "BAT_3") (pintype "output"))
    )
    (net (code "70") (name "Net-(LED1-PadC)") (class "Default")
      (node (ref "LED1") (pin "C") (pinfunction "C_C") (pintype "passive"))
      (node (ref "R25") (pin "1") (pinfunction "1_1") (pintype "passive"))
    )
    (net (code "71") (name "Net-(LED2-PadC)") (class "Default")
      (node (ref "LED2") (pin "C") (pinfunction "C_C") (pintype "passive"))
      (node (ref "R70") (pin "2") (pinfunction "2_2") (pintype "passive"))
    )
    (net (code "72") (name "Net-(LED3-PadC)") (class "Default")
      (node (ref "LED3") (pin "C") (pinfunction "C_C") (pintype "passive"))
      (node (ref "R69") (pin "2") (pinfunction "2_2") (pintype "passive"))
    )
    (net (code "73") (name "Net-(Q2-B)") (class "Default")
      (node (ref "D17") (pin "C") (pinfunction "C_C") (pintype "passive"))
      (node (ref "Q2") (pin "1") (pinfunction "B_1") (pintype "passive"))
      (node (ref "R66") (pin "2") (pinfunction "2_2") (pintype "passive"))
      (node (ref "R68") (pin "2") (pinfunction "2_2") (pintype "passive"))
    )
    (net (code "74") (name "Net-(Q3-PadB)") (class "Default")
      (node (ref "Q3") (pin "B") (pinfunction "B_B") (pintype "passive"))
      (node (ref "R17") (pin "2") (pinfunction "2_2") (pintype "passive"))
    )
    (net (code "75") (name "Net-(Q4-PadB)") (class "Default")
      (node (ref "Q4") (pin "B") (pinfunction "B_B") (pintype "passive"))
      (node (ref "R16") (pin "2") (pinfunction "2_2") (pintype "passive"))
    )
    (net (code "76") (name "Net-(Q5-B)") (class "Default")
      (node (ref "Q5") (pin "1") (pinfunction "B_1") (pintype "passive"))
      (node (ref "R55") (pin "1") (pinfunction "1_1") (pintype "passive"))
      (node (ref "R56") (pin "1") (pinfunction "1_1") (pintype "passive"))
    )
    (net (code "77") (name "Net-(Q6-PadB)") (class "Default")
      (node (ref "Q6") (pin "B") (pinfunction "B_B") (pintype "passive"))
      (node (ref "R19") (pin "2") (pinfunction "2_2") (pintype "passive"))
    )
    (net (code "78") (name "Net-(Q7-PadB)") (class "Default")
      (node (ref "Q7") (pin "B") (pinfunction "B_B") (pintype "passive"))
      (node (ref "R18") (pin "2") (pinfunction "2_2") (pintype "passive"))
    )
    (net (code "79") (name "Net-(Q8-PadB)") (class "Default")
      (node (ref "Q8") (pin "B") (pinfunction "B_B") (pintype "passive"))
      (node (ref "R33") (pin "1") (pinfunction "1_1") (pintype "passive"))
      (node (ref "R39") (pin "2") (pinfunction "2_2") (pintype "passive"))
    )
    (net (code "80") (name "Net-(Q9-PadB)") (class "Default")
      (node (ref "Q9") (pin "B") (pinfunction "B_B") (pintype "passive"))
      (node (ref "R36") (pin "1") (pinfunction "1_1") (pintype "passive"))
      (node (ref "R40") (pin "2") (pinfunction "2_2") (pintype "passive"))
    )
    (net (code "81") (name "Net-(Q10-PadB)") (class "Default")
      (node (ref "Q10") (pin "B") (pinfunction "B_B") (pintype "passive"))
      (node (ref "R34") (pin "1") (pinfunction "1_1") (pintype "passive"))
      (node (ref "R41") (pin "2") (pinfunction "2_2") (pintype "passive"))
    )
    (net (code "82") (name "Net-(Q11-PadB)") (class "Default")
      (node (ref "Q11") (pin "B") (pinfunction "B_B") (pintype "passive"))
      (node (ref "R35") (pin "1") (pinfunction "1_1") (pintype "passive"))
      (node (ref "R42") (pin "2") (pinfunction "2_2") (pintype "passive"))
    )
    (net (code "83") (name "Net-(Q12-C)") (class "Default")
      (node (ref "Q12") (pin "3") (pinfunction "C_3") (pintype "passive"))
      (node (ref "Q13") (pin "1") (pinfunction "B_1") (pintype "passive"))
      (node (ref "R31") (pin "2") (pinfunction "2_2") (pintype "passive"))
    )
    (net (code "84") (name "Net-(Q13-C)") (class "Default")
      (node (ref "Q13") (pin "3") (pinfunction "C_3") (pintype "passive"))
      (node (ref "R37") (pin "2") (pinfunction "2_2") (pintype "passive"))
    )
    (net (code "85") (name "Net-(SIM1-PRS)") (class "Default")
      (node (ref "SIM1") (pin "4") (pinfunction "PRS_4") (pintype "bidirectional"))
      (node (ref "SIM2") (pin "C8") (pinfunction "PRESENCE_C8") (pintype "bidirectional"))
    )
    (net (code "86") (name "Net-(SIM1-VPP)") (class "Default")
      (node (ref "SIM1") (pin "2") (pinfunction "VPP_2") (pintype "bidirectional"))
      (node (ref "SIM2") (pin "C6") (pinfunction "VPP_C6") (pintype "bidirectional"))
    )
    (net (code "87") (name "Net-(U$1-RXD)") (class "Default")
      (node (ref "D3") (pin "A") (pinfunction "A_A") (pintype "passive"))
      (node (ref "R26") (pin "2") (pinfunction "2_2") (pintype "passive"))
      (node (ref "U$1") (pin "1") (pinfunction "RXD_1") (pintype "bidirectional"))
    )
    (net (code "88") (name "Net-(U$1-V_BCKP)") (class "Default")
      (node (ref "R29") (pin "1") (pinfunction "1_1") (pintype "passive"))
      (node (ref "U$1") (pin "5") (pinfunction "V_BCKP_5") (pintype "bidirectional"))
    )
    (net (code "89") (name "Net-(U$1-WAKE_UP)") (class "Default")
      (node (ref "R84") (pin "1") (pinfunction "1_1") (pintype "passive"))
      (node (ref "U$1") (pin "7") (pinfunction "WAKE_UP_7") (pintype "bidirectional"))
    )
    (net (code "90") (name "Net-(U$3-ADJ)") (class "Default")
      (node (ref "R86") (pin "2") (pinfunction "2_2") (pintype "passive"))
      (node (ref "R87") (pin "1") (pinfunction "1_1") (pintype "passive"))
      (node (ref "U$3") (pin "2") (pinfunction "ADJ_2") (pintype "bidirectional"))
    )
    (net (code "91") (name "Net-(U1-RS)") (class "Default")
      (node (ref "R1") (pin "2") (pinfunction "2_2") (pintype "passive"))
      (node (ref "U1") (pin "8") (pinfunction "RS_8") (pintype "bidirectional"))
    )
    (net (code "92") (name "Net-(U2A-BOOT0)") (class "Default")
      (node (ref "R6") (pin "1") (pinfunction "1_1") (pintype "passive"))
      (node (ref "U2") (pin "44") (pinfunction "BOOT0_44") (pintype "input"))
    )
    (net (code "93") (name "Net-(U2A-NRST)") (class "Default")
      (node (ref "C12") (pin "1") (pinfunction "1_1") (pintype "passive"))
      (node (ref "C57") (pin "1") (pinfunction "1_1") (pintype "passive"))
      (node (ref "R67") (pin "2") (pinfunction "2_2") (pintype "passive"))
      (node (ref "U2") (pin "7") (pinfunction "NRST_7") (pintype "bidirectional"))
    )
    (net (code "94") (name "Net-(U2A-OSC_IN)") (class "Default")
      (node (ref "C1") (pin "2") (pinfunction "2_2") (pintype "passive"))
      (node (ref "Q1") (pin "1") (pinfunction "1_1") (pintype "passive"))
      (node (ref "U2") (pin "5") (pinfunction "OSC_IN_5") (pintype "bidirectional"))
    )
    (net (code "95") (name "Net-(U2A-OSC_OUT)") (class "Default")
      (node (ref "C2") (pin "2") (pinfunction "2_2") (pintype "passive"))
      (node (ref "Q1") (pin "2") (pinfunction "2_2") (pintype "passive"))
      (node (ref "U2") (pin "6") (pinfunction "OSC_OUT_6") (pintype "bidirectional"))
    )
    (net (code "96") (name "Net-(U2A-PB2)") (class "Default")
      (node (ref "R5") (pin "2") (pinfunction "2_2") (pintype "passive"))
      (node (ref "U2") (pin "20") (pinfunction "PB2_20") (pintype "bidirectional"))
    )
    (net (code "97") (name "Net-(U4-CHRG)") (class "Default")
      (node (ref "R65") (pin "1") (pinfunction "1_1") (pintype "passive"))
      (node (ref "U4") (pin "1") (pinfunction "CHRG_1") (pintype "output"))
    )
    (net (code "98") (name "Net-(U4-PROG)") (class "Default")
      (node (ref "R30") (pin "1") (pinfunction "1_1") (pintype "passive"))
      (node (ref "U4") (pin "5") (pinfunction "PROG_5") (pintype "input"))
    )
    (net (code "99") (name "Net-(U5-AVDD)") (class "Default")
      (node (ref "R73") (pin "1") (pinfunction "1_1") (pintype "passive"))
      (node (ref "U5") (pin "8") (pinfunction "AVDD_8") (pintype "bidirectional"))
    )
    (net (code "100") (name "Net-(U5-RXD)") (class "Default")
      (node (ref "J8") (pin "2") (pinfunction "2_2") (pintype "passive"))
      (node (ref "U5") (pin "18") (pinfunction "RXD_18") (pintype "bidirectional"))
    )
    (net (code "101") (name "Net-(U5-SIM_CLK)") (class "Default")
      (node (ref "R72") (pin "1") (pinfunction "1_1") (pintype "passive"))
      (node (ref "U5") (pin "13") (pinfunction "SIM_CLK_13") (pintype "bidirectional"))
    )
    (net (code "102") (name "Net-(U5-SIM_DATA)") (class "Default")
      (node (ref "R74") (pin "1") (pinfunction "1_1") (pintype "passive"))
      (node (ref "U5") (pin "11") (pinfunction "SIM_DATA_11") (pintype "bidirectional"))
    )
    (net (code "103") (name "Net-(U5-SIM_RST)") (class "Default")
      (node (ref "R75") (pin "1") (pinfunction "1_1") (pintype "passive"))
      (node (ref "U5") (pin "12") (pinfunction "SIM_RST_12") (pintype "bidirectional"))
    )
    (net (code "104") (name "Net-(U5-TXD)") (class "Default")
      (node (ref "J8") (pin "1") (pinfunction "1_1") (pintype "passive"))
      (node (ref "U5") (pin "17") (pinfunction "TXD_17") (pintype "bidirectional"))
    )
    (net (code "105") (name "Net-(U5-VRTC)") (class "Default")
      (node (ref "D18") (pin "C") (pinfunction "C_C") (pintype "passive"))
      (node (ref "U5") (pin "44") (pinfunction "VRTC_44") (pintype "bidirectional"))
    )
    (net (code "106") (name "Net-(U6-~{WP}(IO2))") (class "Default")
      (node (ref "R71") (pin "1") (pinfunction "1_1") (pintype "passive"))
      (node (ref "U6") (pin "3") (pinfunction "~{WP}(IO2)_3") (pintype "bidirectional"))
    )
    (net (code "107") (name "Net-(U7-C1+)") (class "Default")
      (node (ref "C32") (pin "1") (pinfunction "1_1") (pintype "passive"))
      (node (ref "U7") (pin "1") (pinfunction "C1+_1") (pintype "bidirectional"))
    )
    (net (code "108") (name "Net-(U7-C1-)") (class "Default")
      (node (ref "C32") (pin "2") (pinfunction "2_2") (pintype "passive"))
      (node (ref "U7") (pin "3") (pinfunction "C1-_3") (pintype "bidirectional"))
    )
    (net (code "109") (name "Net-(U7-C2+)") (class "Default")
      (node (ref "C56") (pin "1") (pinfunction "1_1") (pintype "passive"))
      (node (ref "U7") (pin "4") (pinfunction "C2+_4") (pintype "bidirectional"))
    )
    (net (code "110") (name "Net-(U7-C2-)") (class "Default")
      (node (ref "C56") (pin "2") (pinfunction "2_2") (pintype "passive"))
      (node (ref "U7") (pin "5") (pinfunction "C2-_5") (pintype "bidirectional"))
    )
    (net (code "111") (name "Net-(U7-V+)") (class "Default")
      (node (ref "C54") (pin "2") (pinfunction "2_2") (pintype "passive"))
      (node (ref "U7") (pin "2") (pinfunction "V+_2") (pintype "bidirectional"))
    )
    (net (code "112") (name "Net-(U7-V-)") (class "Default")
      (node (ref "C55") (pin "1") (pinfunction "1_1") (pintype "passive"))
      (node (ref "U7") (pin "6") (pinfunction "V-_6") (pintype "bidirectional"))
    )
    (net (code "113") (name "Net-(U8-POL)") (class "Default")
      (node (ref "R43") (pin "1") (pinfunction "1_1") (pintype "passive"))
      (node (ref "R9") (pin "2") (pinfunction "2_2") (pintype "passive"))
      (node (ref "U8") (pin "4") (pinfunction "VDD_4") (pintype "power_in"))
      (node (ref "U8") (pin "5") (pinfunction "VPP_5") (pintype "power_in"))
      (node (ref "U8") (pin "6") (pinfunction "POL_6") (pintype "input"))
    )
    (net (code "114") (name "Net-(U8-RXD)") (class "Default")
      (node (ref "D1") (pin "A") (pinfunction "A_A") (pintype "passive"))
      (node (ref "R9") (pin "1") (pinfunction "1_1") (pintype "passive"))
      (node (ref "U8") (pin "8") (pinfunction "RXD_8") (pintype "output"))
    )
    (net (code "115") (name "Net-(U8-TXD)") (class "Default")
      (node (ref "R10") (pin "1") (pinfunction "1_1") (pintype "passive"))
      (node (ref "U8") (pin "7") (pinfunction "TXD_7") (pintype "input"))
    )
    (net (code "116") (name "Net-(U9A-AD0)") (class "Default")
      (node (ref "R14") (pin "1") (pinfunction "1_1") (pintype "passive"))
      (node (ref "U9") (pin "9") (pinfunction "AD0_9") (pintype "input"))
    )
    (net (code "117") (name "Net-(U9A-CPOUT)") (class "Default")
      (node (ref "C60") (pin "1") (pinfunction "1_1") (pintype "passive"))
      (node (ref "U9") (pin "20") (pinfunction "CPOUT_20") (pintype "output"))
    )
    (net (code "118") (name "Net-(U9A-REGOUT)") (class "Default")
      (node (ref "C62") (pin "1") (pinfunction "1_1") (pintype "passive"))
      (node (ref "U9") (pin "10") (pinfunction "REGOUT_10") (pintype "output"))
    )
    (net (code "119") (name "Net-(U10-BST)") (class "Default")
      (node (ref "C35") (pin "2") (pinfunction "2_2") (pintype "passive"))
      (node (ref "U10") (pin "8") (pinfunction "BST_8") (pintype "bidirectional"))
    )
    (net (code "120") (name "Net-(U10-COMP)") (class "Default")
      (node (ref "C34") (pin "1") (pinfunction "1_1") (pintype "passive"))
      (node (ref "C36") (pin "1") (pinfunction "1_1") (pintype "passive"))
      (node (ref "U10") (pin "3") (pinfunction "COMP_3") (pintype "bidirectional"))
    )
    (net (code "121") (name "Net-(U10-EN)") (class "Default")
      (node (ref "R59") (pin "1") (pinfunction "1_1") (pintype "passive"))
      (node (ref "R60") (pin "1") (pinfunction "1_1") (pintype "passive"))
      (node (ref "U10") (pin "2") (pinfunction "EN_2") (pintype "bidirectional"))
    )
    (net (code "122") (name "Net-(U10-FB)") (class "Default")
      (node (ref "R62") (pin "2") (pinfunction "2_2") (pintype "passive"))
      (node (ref "R63") (pin "2") (pinfunction "2_2") (pintype "passive"))
      (node (ref "U10") (pin "4") (pinfunction "FB_4") (pintype "bidirectional"))
    )
    (net (code "123") (name "Net-(U10-FREQ)") (class "Default")
      (node (ref "R61") (pin "1") (pinfunction "1_1") (pintype "passive"))
      (node (ref "U10") (pin "6") (pinfunction "FREQ_6") (pintype "bidirectional"))
    )
    (net (code "124") (name "Net-(U10-SW)") (class "Default")
      (node (ref "C35") (pin "1") (pinfunction "1_1") (pintype "passive"))
      (node (ref "D15") (pin "C") (pinfunction "C_C") (pintype "passive"))
      (node (ref "D9") (pin "C") (pinfunction "C_C") (pintype "passive"))
      (node (ref "L2") (pin "2") (pinfunction "2_2") (pintype "passive"))
      (node (ref "U10") (pin "1") (pinfunction "SW_1") (pintype "bidirectional"))
    )
    (net (code "125") (name "PWR_IND") (class "Default")
      (node (ref "Q2") (pin "3") (pinfunction "C_3") (pintype "passive"))
      (node (ref "R44") (pin "2") (pinfunction "2_2") (pintype "passive"))
      (node (ref "U5") (pin "23") (pinfunction "RTS_23") (pintype "bidirectional"))
    )
    (net (code "126") (name "PWR_KEY") (class "Default")
      (node (ref "J8") (pin "4") (pinfunction "4_4") (pintype "passive"))
      (node (ref "Q5") (pin "3") (pinfunction "C_3") (pintype "passive"))
      (node (ref "R57") (pin "2") (pinfunction "2_2") (pintype "passive"))
      (node (ref "U5") (pin "7") (pinfunction "PWRKEY_7") (pintype "bidirectional"))
    )
    (net (code "127") (name "RS232_RX2") (class "Default")
      (node (ref "U2") (pin "12") (pinfunction "PA2_12") (pintype "bidirectional"))
      (node (ref "U7") (pin "10") (pinfunction "DIN2_10") (pintype "bidirectional"))
    )
    (net (code "128") (name "RS232_TX2") (class "Default")
      (node (ref "U2") (pin "13") (pinfunction "PA3_13") (pintype "bidirectional"))
      (node (ref "U7") (pin "9") (pinfunction "ROUT2_9") (pintype "bidirectional"))
    )
    (net (code "129") (name "RX3") (class "Default")
      (node (ref "D1") (pin "C") (pinfunction "C_C") (pintype "passive"))
      (node (ref "U2") (pin "21") (pinfunction "PB10_21") (pintype "bidirectional"))
    )
    (net (code "130") (name "RXD") (class "Default")
      (node (ref "J6") (pin "2") (pinfunction "2_2") (pintype "passive"))
      (node (ref "U7") (pin "7") (pinfunction "DOUT2_7") (pintype "bidirectional"))
    )
    (net (code "131") (name "SCK_SF") (class "Default")
      (node (ref "U5") (pin "32") (pinfunction "PCM_IN_32") (pintype "bidirectional"))
      (node (ref "U6") (pin "6") (pinfunction "CLK_6") (pintype "input"))
    )
    (net (code "132") (name "SCL1") (class "Default")
      (node (ref "J4") (pin "1") (pinfunction "1_1") (pintype "passive"))
      (node (ref "R13") (pin "1") (pinfunction "1_1") (pintype "passive"))
      (node (ref "U2") (pin "42") (pinfunction "PB6_42") (pintype "bidirectional"))
      (node (ref "U9") (pin "23") (pinfunction "SCL_23") (pintype "input"))
    )
    (net (code "133") (name "SDA1") (class "Default")
      (node (ref "J4") (pin "2") (pinfunction "2_2") (pintype "passive"))
      (node (ref "R12") (pin "1") (pinfunction "1_1") (pintype "passive"))
      (node (ref "U2") (pin "43") (pinfunction "PB7_43") (pintype "bidirectional"))
      (node (ref "U9") (pin "24") (pinfunction "SDA_24") (pintype "bidirectional"))
    )
    (net (code "134") (name "SIM_CLK") (class "Default")
      (node (ref "C49") (pin "1") (pinfunction "1_1") (pintype "passive"))
      (node (ref "R72") (pin "2") (pinfunction "2_2") (pintype "passive"))
      (node (ref "SIM1") (pin "6") (pinfunction "CLK_6") (pintype "bidirectional"))
      (node (ref "SIM2") (pin "C3") (pinfunction "CLK_C3") (pintype "bidirectional"))
      (node (ref "U12") (pin "4") (pinfunction "3_4") (pintype "bidirectional"))
    )
    (net (code "135") (name "SIM_DATA") (class "Default")
      (node (ref "C46") (pin "1") (pinfunction "1_1") (pintype "passive"))
      (node (ref "R74") (pin "2") (pinfunction "2_2") (pintype "passive"))
      (node (ref "SIM1") (pin "3") (pinfunction "DATA_3") (pintype "bidirectional"))
      (node (ref "SIM2") (pin "C7") (pinfunction "I/O_C7") (pintype "bidirectional"))
      (node (ref "U12") (pin "6") (pinfunction "5_6") (pintype "bidirectional"))
    )
    (net (code "136") (name "SIM_GND") (class "Default")
      (node (ref "C47") (pin "2") (pinfunction "2_2") (pintype "passive"))
      (node (ref "SIM1") (pin "1") (pinfunction "GND_1") (pintype "bidirectional"))
      (node (ref "SIM1") (pin "5") (pinfunction "GND1_5") (pintype "bidirectional"))
      (node (ref "SIM1") (pin "PAD") (pinfunction "PAD_PAD") (pintype "bidirectional"))
      (node (ref "SIM2") (pin "C4") (pinfunction "GND_C4") (pintype "bidirectional"))
      (node (ref "SIM2") (pin "C5") (pinfunction "GND_C5") (pintype "bidirectional"))
      (node (ref "U5") (pin "10") (pinfunction "SIM_GND_10") (pintype "bidirectional"))
    )
    (net (code "137") (name "SIM_RST") (class "Default")
      (node (ref "C48") (pin "1") (pinfunction "1_1") (pintype "passive"))
      (node (ref "R75") (pin "2") (pinfunction "2_2") (pintype "passive"))
      (node (ref "SIM1") (pin "7") (pinfunction "RST_7") (pintype "bidirectional"))
      (node (ref "SIM2") (pin "C2") (pinfunction "RST_C2") (pintype "bidirectional"))
      (node (ref "U12") (pin "5") (pinfunction "4_5") (pintype "bidirectional"))
    )
    (net (code "138") (name "SIM_VDD") (class "Default")
      (node (ref "C47") (pin "1") (pinfunction "1_1") (pintype "passive"))
      (node (ref "C50") (pin "1") (pinfunction "1_1") (pintype "passive"))
      (node (ref "SIM1") (pin "8") (pinfunction "VDD_8") (pintype "bidirectional"))
      (node (ref "SIM2") (pin "C1") (pinfunction "VCC_C1") (pintype "bidirectional"))
      (node (ref "U12") (pin "3") (pinfunction "2_3") (pintype "bidirectional"))
      (node (ref "U5") (pin "14") (pinfunction "SIM_VDD_14") (pintype "bidirectional"))
    )
    (net (code "139") (name "SPK1N") (class "Default")
      (node (ref "C21") (pin "2") (pinfunction "2_2") (pintype "passive"))
      (node (ref "C22") (pin "1") (pinfunction "1_1") (pintype "passive"))
      (node (ref "C24") (pin "2") (pinfunction "2_2") (pintype "passive"))
      (node (ref "C25") (pin "1") (pinfunction "1_1") (pintype "passive"))
      (node (ref "J15") (pin "4") (pinfunction "4_4") (pintype "passive"))
      (node (ref "U5") (pin "6") (pinfunction "SPK1N_6") (pintype "bidirectional"))
    )
    (net (code "140") (name "SPK1P") (class "Default")
      (node (ref "C20") (pin "2") (pinfunction "2_2") (pintype "passive"))
      (node (ref "C21") (pin "1") (pinfunction "1_1") (pintype "passive"))
      (node (ref "C23") (pin "2") (pinfunction "2_2") (pintype "passive"))
      (node (ref "C24") (pin "1") (pinfunction "1_1") (pintype "passive"))
      (node (ref "J15") (pin "3") (pinfunction "3_3") (pintype "passive"))
      (node (ref "U5") (pin "5") (pinfunction "SPK1P_5") (pintype "bidirectional"))
    )
    (net (code "141") (name "SW") (class "Default")
      (node (ref "R58") (pin "2") (pinfunction "2_2") (pintype "passive"))
      (node (ref "SW1") (pin "1") (pinfunction "2_1") (pintype "passive"))
      (node (ref "SW1") (pin "2") (pinfunction "2_2") (pintype "passive"))
      (node (ref "U2") (pin "17") (pinfunction "PA7_17") (pintype "bidirectional"))
    )
    (net (code "142") (name "SWCLK") (class "Default")
      (node (ref "J10") (pin "2") (pinfunction "2_2") (pintype "passive"))
      (node (ref "U2") (pin "37") (pinfunction "PA14_37") (pintype "bidirectional"))
    )
    (net (code "143") (name "SWO") (class "Default")
      (node (ref "J10") (pin "3") (pinfunction "3_3") (pintype "passive"))
      (node (ref "U2") (pin "34") (pinfunction "PA13_34") (pintype "bidirectional"))
    )
    (net (code "144") (name "T1") (class "Default")
      (node (ref "JP4") (pin "2") (pinfunction "2_2") (pintype "passive"))
      (node (ref "Q12") (pin "1") (pinfunction "B_1") (pintype "passive"))
      (node (ref "R32") (pin "2") (pinfunction "2_2") (pintype "passive"))
      (node (ref "U$1") (pin "2") (pinfunction "TXD_2") (pintype "bidirectional"))
    )
    (net (code "145") (name "TX3") (class "Default")
      (node (ref "R10") (pin "2") (pinfunction "2_2") (pintype "passive"))
      (node (ref "U2") (pin "22") (pinfunction "PB11_22") (pintype "bidirectional"))
    )
    (net (code "146") (name "TXD") (class "Default")
      (node (ref "J6") (pin "1") (pinfunction "1_1") (pintype "passive"))
      (node (ref "U7") (pin "8") (pinfunction "RIN2_8") (pintype "bidirectional"))
    )
    (net (code "147") (name "USB_DN") (class "Default")
      (node (ref "R7") (pin "1") (pinfunction "1_1") (pintype "passive"))
      (node (ref "U2") (pin "32") (pinfunction "PA11_32") (pintype "bidirectional"))
    )
    (net (code "148") (name "USB_DP") (class "Default")
      (node (ref "R11") (pin "2") (pinfunction "2_2") (pintype "passive"))
      (node (ref "R8") (pin "1") (pinfunction "1_1") (pintype "passive"))
      (node (ref "U2") (pin "33") (pinfunction "PA12_33") (pintype "bidirectional"))
    )
    (net (code "149") (name "VBAT_EXT") (class "Default")
      (node (ref "J3") (pin "1") (pinfunction "1_1") (pintype "passive"))
      (node (ref "MOV1") (pin "2") (pinfunction "MOV_2") (pintype "passive"))
      (node (ref "U11") (pin "4") (pinfunction "AC_2_4") (pintype "input"))
    )
    (net (code "150") (name "VBAT_GND") (class "Default")
      (node (ref "J3") (pin "2") (pinfunction "2_2") (pintype "passive"))
      (node (ref "MOV1") (pin "1") (pinfunction "FUSE_1") (pintype "passive"))
      (node (ref "U11") (pin "3") (pinfunction "AC_3") (pintype "input"))
    )
    (net (code "151") (name "VCC") (class "Default")
      (node (ref "C3") (pin "1") (pinfunction "1_1") (pintype "passive"))
      (node (ref "C4") (pin "1") (pinfunction "1_1") (pintype "passive"))
      (node (ref "C40") (pin "1") (pinfunction "1_1") (pintype "passive"))
      (node (ref "C45") (pin "1") (pinfunction "1_1") (pintype "passive"))
      (node (ref "C5") (pin "1") (pinfunction "1_1") (pintype "passive"))
      (node (ref "C54") (pin "1") (pinfunction "1_1") (pintype "passive"))
      (node (ref "C58") (pin "1") (pinfunction "1_1") (pintype "passive"))
      (node (ref "C6") (pin "1") (pinfunction "1_1") (pintype "passive"))
      (node (ref "C63") (pin "1") (pinfunction "1_1") (pintype "passive"))
      (node (ref "C7") (pin "1") (pinfunction "1_1") (pintype "passive"))
      (node (ref "C8") (pin "1") (pinfunction "1_1") (pintype "passive"))
      (node (ref "C9") (pin "1") (pinfunction "1_1") (pintype "passive"))
      (node (ref "D19") (pin "C") (pinfunction "C_C") (pintype "passive"))
      (node (ref "J10") (pin "4") (pinfunction "4_4") (pintype "passive"))
      (node (ref "JP1") (pin "1") (pinfunction "1_1") (pintype "passive"))
      (node (ref "R11") (pin "1") (pinfunction "1_1") (pintype "passive"))
      (node (ref "R12") (pin "2") (pinfunction "2_2") (pintype "passive"))
      (node (ref "R13") (pin "2") (pinfunction "2_2") (pintype "passive"))
      (node (ref "R26") (pin "1") (pinfunction "1_1") (pintype "passive"))
      (node (ref "R31") (pin "1") (pinfunction "1_1") (pintype "passive"))
      (node (ref "R32") (pin "1") (pinfunction "1_1") (pintype "passive"))
      (node (ref "R37") (pin "1") (pinfunction "1_1") (pintype "passive"))
      (node (ref "R58") (pin "1") (pinfunction "1_1") (pintype "passive"))
      (node (ref "R67") (pin "1") (pinfunction "1_1") (pintype "passive"))
      (node (ref "R76") (pin "2") (pinfunction "2_2") (pintype "passive"))
      (node (ref "R79") (pin "1") (pinfunction "1_1") (pintype "passive"))
      (node (ref "R80") (pin "1") (pinfunction "1_1") (pintype "passive"))
      (node (ref "R81") (pin "1") (pinfunction "1_1") (pintype "passive"))
      (node (ref "R82") (pin "1") (pinfunction "1_1") (pintype "passive"))
      (node (ref "R83") (pin "2") (pinfunction "2_2") (pintype "passive"))
      (node (ref "U1") (pin "3") (pinfunction "VDD_3") (pintype "bidirectional"))
      (node (ref "U2") (pin "1") (pinfunction "VBAT_1") (pintype "power_in"))
      (node (ref "U2") (pin "9") (pinfunction "VDDA_9") (pintype "power_in"))
      (node (ref "U6") (pin "7") (pinfunction "~{HOLD/RESET}(IO3)_7") (pintype "bidirectional"))
      (node (ref "U6") (pin "8") (pinfunction "VCC_8") (pintype "power_in"))
      (node (ref "U7") (pin "16") (pinfunction "VCC_16") (pintype "power_in"))
      (node (ref "U9") (pin "13") (pinfunction "VDD_13") (pintype "power_in"))
      (node (ref "U9") (pin "8") (pinfunction "VLOGIC_8") (pintype "power_in"))
    )
    (net (code "152") (name "VUSB") (class "Default")
      (node (ref "L1") (pin "2") (pinfunction "2_2") (pintype "passive"))
      (node (ref "R15") (pin "2") (pinfunction "2_2") (pintype "passive"))
    )
    (net (code "153") (name "unconnected-(U$1-1PPS-Pad6)") (class "Default")
      (node (ref "U$1") (pin "6") (pinfunction "1PPS_6") (pintype "bidirectional"))
    )
    (net (code "154") (name "unconnected-(U$1-3D_FIX-Pad9)") (class "Default")
      (node (ref "U$1") (pin "9") (pinfunction "3D_FIX_9") (pintype "bidirectional"))
    )
    (net (code "155") (name "unconnected-(U$1-AADET_N-Pad8)") (class "Default")
      (node (ref "U$1") (pin "8") (pinfunction "AADET_N_8") (pintype "bidirectional"))
    )
    (net (code "156") (name "unconnected-(U$1-EX_ANT-Pad11)") (class "Default")
      (node (ref "U$1") (pin "11") (pinfunction "EX_ANT_11") (pintype "bidirectional"))
    )
    (net (code "157") (name "unconnected-(U$1-GEO_FENCE-Pad14)") (class "Default")
      (node (ref "U$1") (pin "14") (pinfunction "GEO_FENCE_14") (pintype "bidirectional"))
    )
    (net (code "158") (name "unconnected-(U$1-I2CSCK-Pad15)") (class "Default")
      (node (ref "U$1") (pin "15") (pinfunction "I2CSCK_15") (pintype "bidirectional"))
    )
    (net (code "159") (name "unconnected-(U$1-I2CSDK-Pad16)") (class "Default")
      (node (ref "U$1") (pin "16") (pinfunction "I2CSDK_16") (pintype "bidirectional"))
    )
    (net (code "160") (name "unconnected-(U$1-JAM_IND-Pad13)") (class "Default")
      (node (ref "U$1") (pin "13") (pinfunction "JAM_IND_13") (pintype "bidirectional"))
    )
    (net (code "161") (name "unconnected-(U$1-RESET-Pad10)") (class "Default")
      (node (ref "U$1") (pin "10") (pinfunction "RESET_10") (pintype "bidirectional"))
    )
    (net (code "162") (name "unconnected-(U$3-PG-Pad4)") (class "Default")
      (node (ref "U$3") (pin "4") (pinfunction "PG_4") (pintype "bidirectional"))
    )
    (net (code "163") (name "unconnected-(U$4-ADJ-Pad4)") (class "Default")
      (node (ref "U$4") (pin "4") (pinfunction "ADJ_4") (pintype "bidirectional"))
    )
    (net (code "164") (name "unconnected-(U1-VREF-Pad5)") (class "Default")
      (node (ref "U1") (pin "5") (pinfunction "VREF_5") (pintype "bidirectional"))
    )
    (net (code "165") (name "unconnected-(U5-BT_ANT-Pad26)") (class "Default")
      (node (ref "U5") (pin "26") (pinfunction "BT_ANT_26") (pintype "bidirectional"))
    )
    (net (code "166") (name "unconnected-(U5-DCD-Pad21)") (class "Default")
      (node (ref "U5") (pin "21") (pinfunction "DCD_21") (pintype "bidirectional"))
    )
    (net (code "167") (name "unconnected-(U5-DTR-Pad19)") (class "Default")
      (node (ref "U5") (pin "19") (pinfunction "DTR_19") (pintype "bidirectional"))
    )
    (net (code "168") (name "unconnected-(U5-RFTXMON-Pad25)") (class "Default")
      (node (ref "U5") (pin "25") (pinfunction "RFTXMON_25") (pintype "bidirectional"))
    )
    (net (code "169") (name "unconnected-(U5-RI-Pad20)") (class "Default")
      (node (ref "U5") (pin "20") (pinfunction "RI_20") (pintype "bidirectional"))
    )
    (net (code "170") (name "unconnected-(U5-SPK2P-Pad2)") (class "Default")
      (node (ref "U5") (pin "2") (pinfunction "SPK2P_2") (pintype "bidirectional"))
    )
    (net (code "171") (name "unconnected-(U5-VDD_EXT-Pad24)") (class "Default")
      (node (ref "U5") (pin "24") (pinfunction "VDD_EXT_24") (pintype "bidirectional"))
    )
    (net (code "172") (name "unconnected-(U7-DIN1-Pad11)") (class "Default")
      (node (ref "U7") (pin "11") (pinfunction "DIN1_11") (pintype "bidirectional"))
    )
    (net (code "173") (name "unconnected-(U7-DOUT1-Pad14)") (class "Default")
      (node (ref "U7") (pin "14") (pinfunction "DOUT1_14") (pintype "bidirectional"))
    )
    (net (code "174") (name "unconnected-(U7-RIN1-Pad13)") (class "Default")
      (node (ref "U7") (pin "13") (pinfunction "RIN1_13") (pintype "bidirectional"))
    )
    (net (code "175") (name "unconnected-(U7-ROUT1-Pad12)") (class "Default")
      (node (ref "U7") (pin "12") (pinfunction "ROUT1_12") (pintype "bidirectional"))
    )
    (net (code "176") (name "unconnected-(U9A-AUX_CL-Pad7)") (class "Default")
      (node (ref "U9") (pin "7") (pinfunction "AUX_CL_7") (pintype "bidirectional"))
    )
    (net (code "177") (name "unconnected-(U9A-AUX_DA-Pad6)") (class "Default")
      (node (ref "U9") (pin "6") (pinfunction "AUX_DA_6") (pintype "bidirectional"))
    )
    (net (code "178") (name "unconnected-(U9A-FSYNC-Pad11)") (class "Default")
      (node (ref "U9") (pin "11") (pinfunction "FSYNC_11") (pintype "input"))
    )
    (net (code "179") (name "unconnected-(U9A-RESV-Pad19)") (class "Default")
      (node (ref "U9") (pin "19") (pinfunction "RESV_19") (pintype "passive"))
    )
    (net (code "180") (name "unconnected-(U9A-RESV-Pad21)") (class "Default")
      (node (ref "U9") (pin "21") (pinfunction "RESV_21") (pintype "passive"))
    )
    (net (code "181") (name "unconnected-(U9A-RESV-Pad22)") (class "Default")
      (node (ref "U9") (pin "22") (pinfunction "RESV_22") (pintype "passive"))
    )
    (net (code "182") (name "unconnected-(U12-Pad1)") (class "Default")
      (node (ref "U12") (pin "1") (pinfunction "1_1") (pintype "bidirectional"))
    )
  )
)
